# Main_Board.net
KiCad netlist of a schematic drawn in Altium Designer
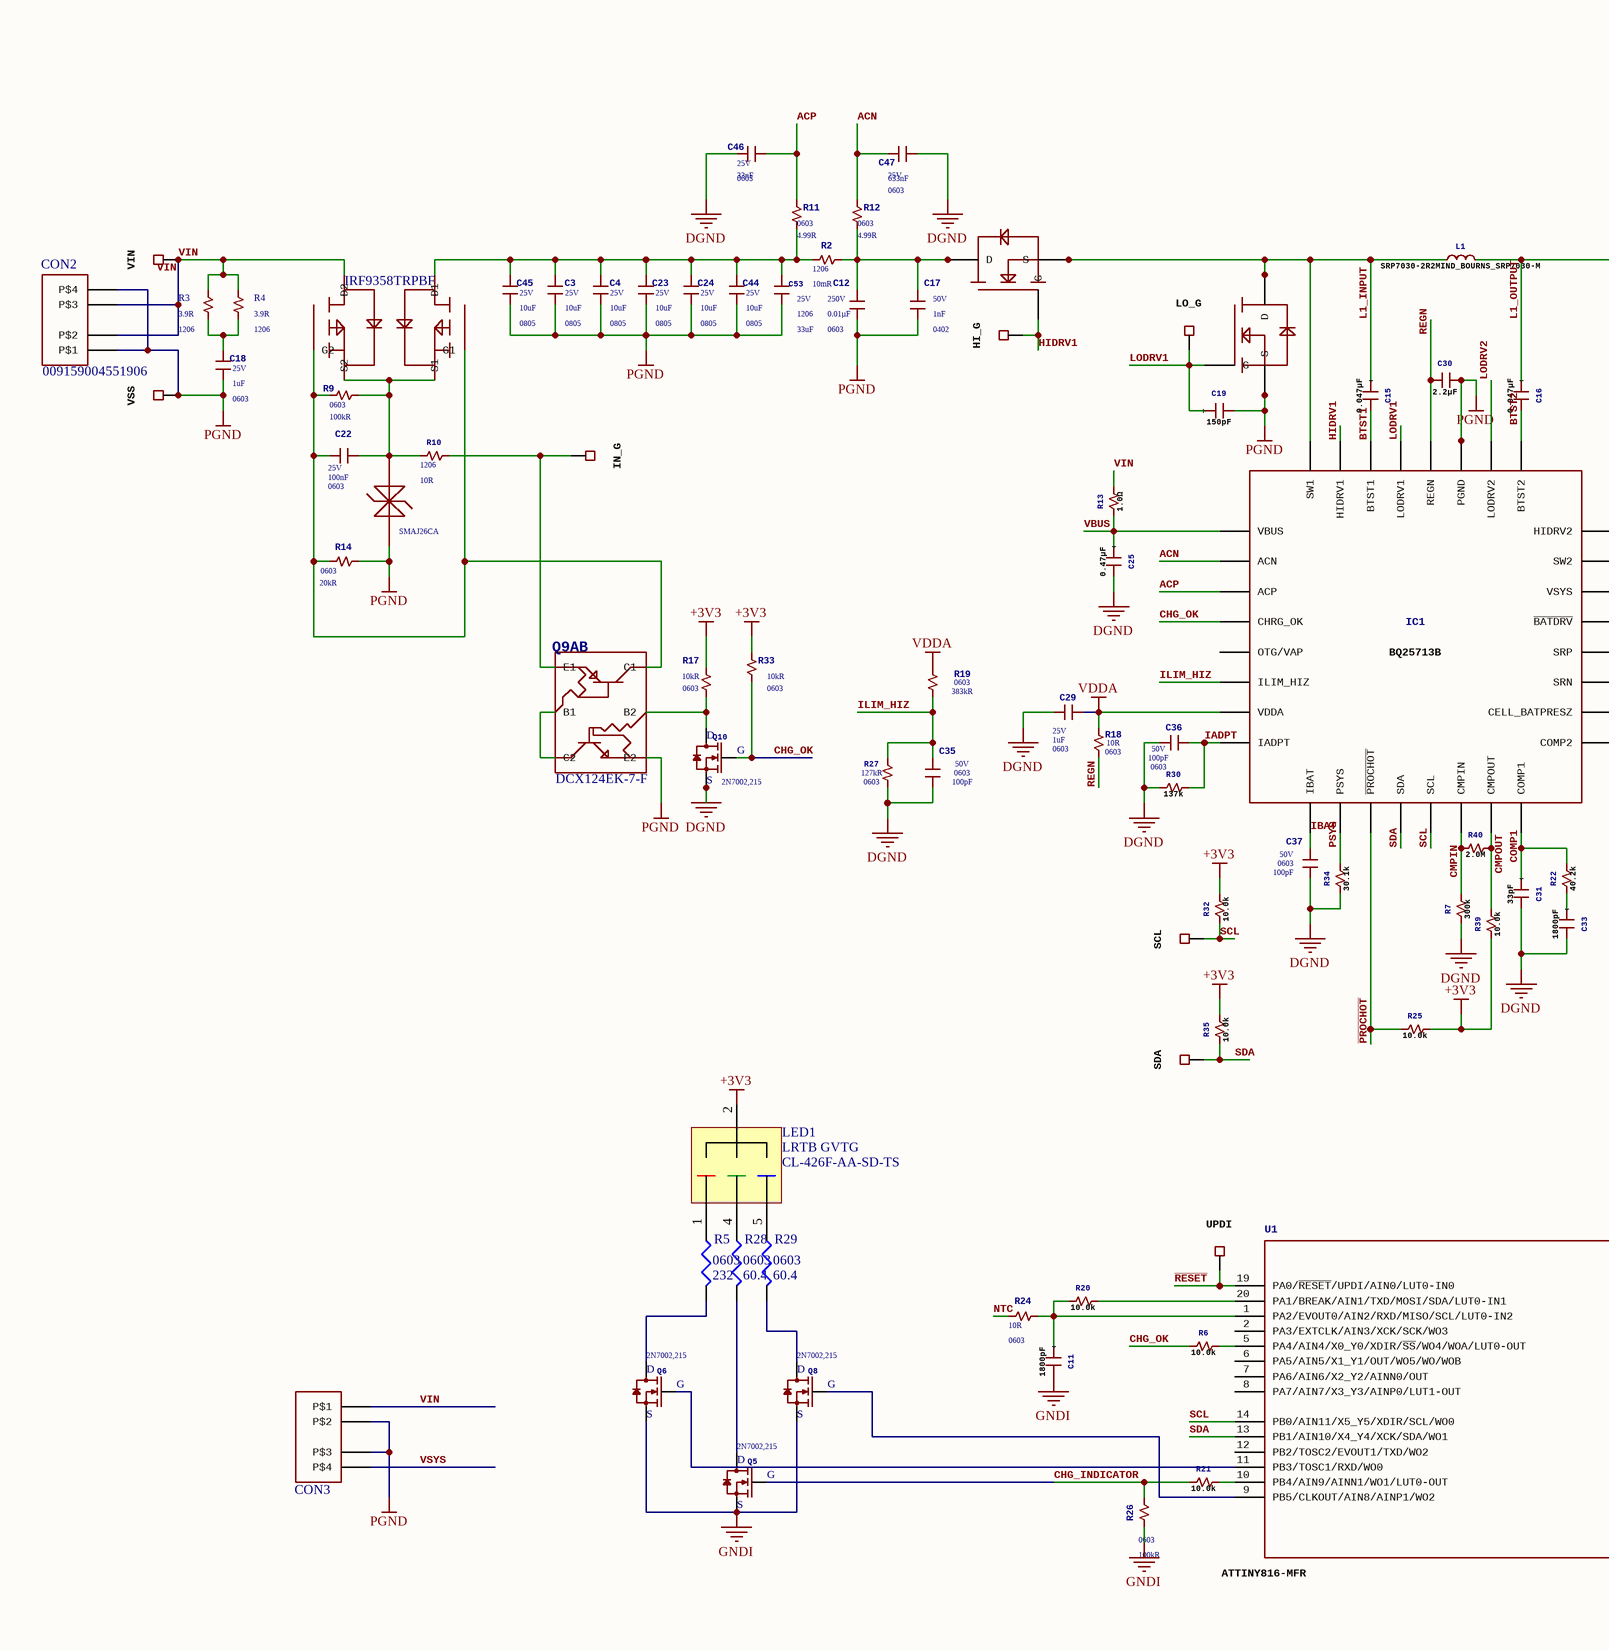
[diagram p0: Main Board.SchDoc, left]
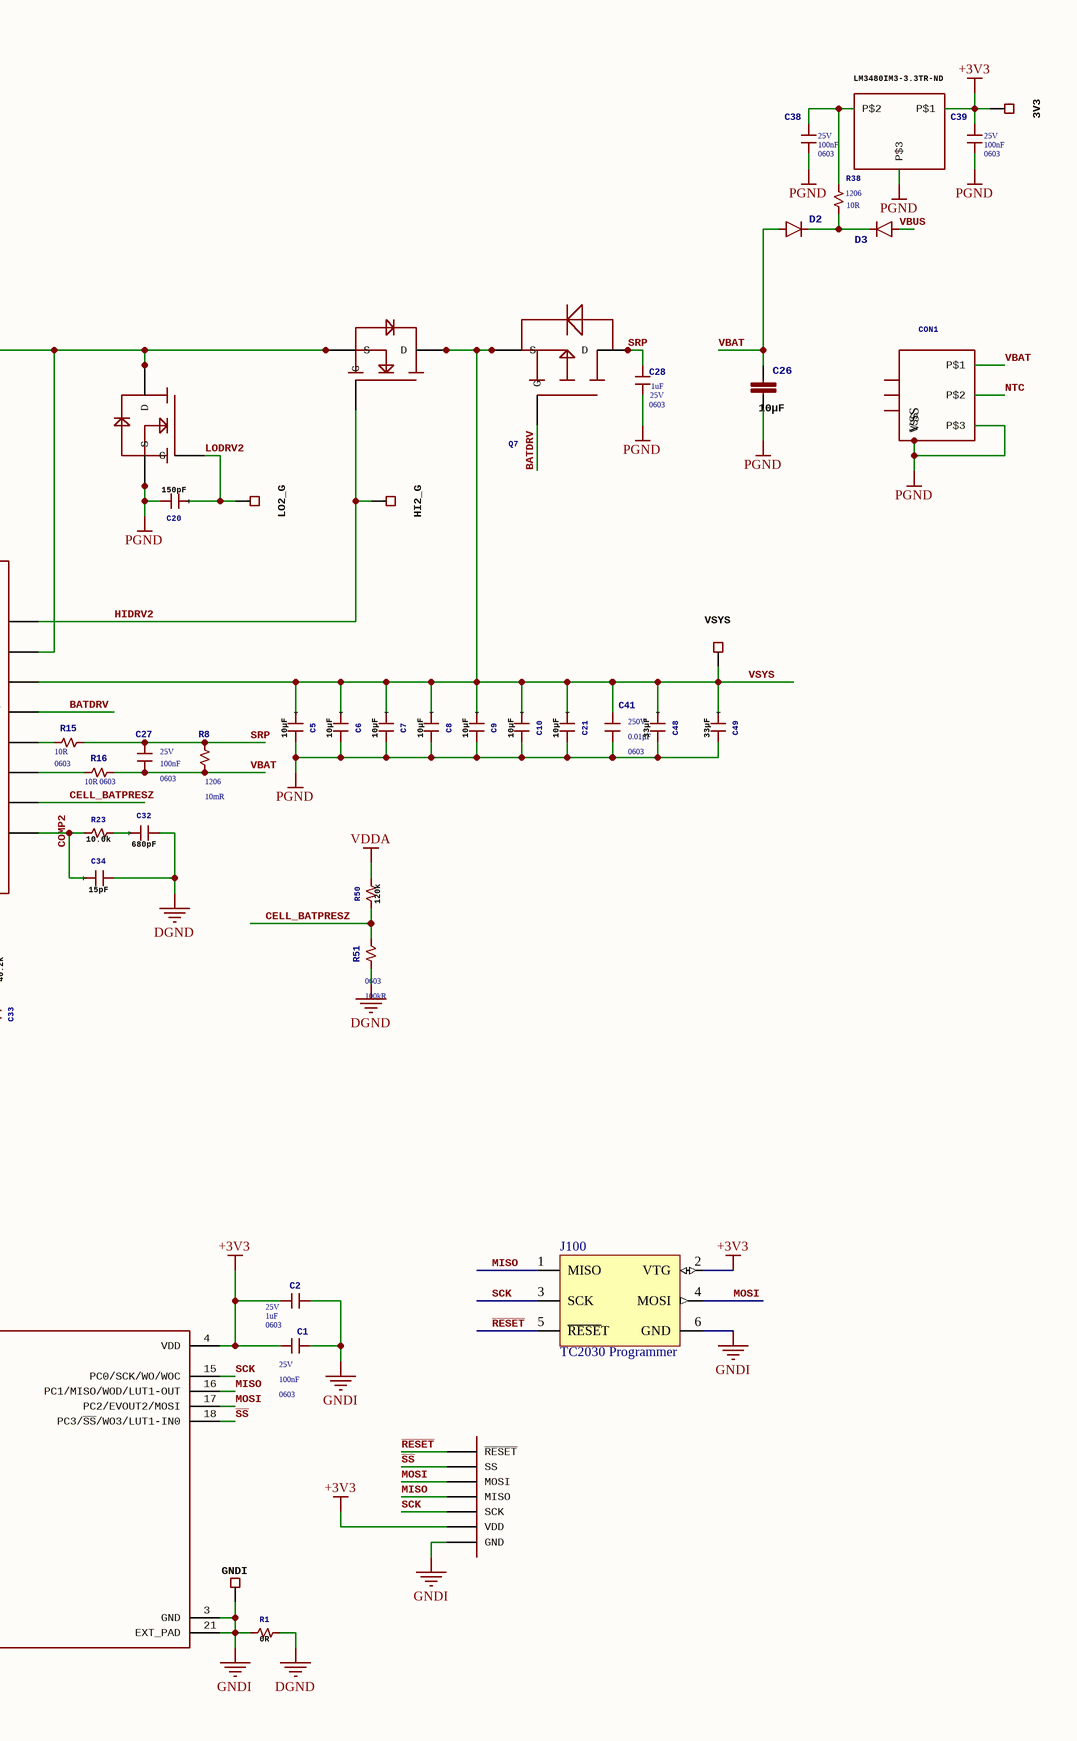
[diagram p1: Main Board.SchDoc, right]

(export (version "E")
  (design (tool "Eeschema 10.0.6"))
  (components
    (comp (ref "C1")
      (value "CAP CER 0.1UF 25V X7R 0603")
      (footprint "Main Board:0603")
      (description "0.1µF ±10% 25V Ceramic Capacitor X7R 0603 (1608 Metric)")
      (fields
        (field (name "MANUFACTURER") "TDK")
        (field (name "MANUFACTURER PART NUMBER") "CGA3E2X7R1E104K080AA")
        (field (name "VOLTAGE RATING") "25V")
        (field (name "CAPACITANCE") "100nF")
        (field (name "CASE/PACKAGE") "0603")
      )
      (libsource (lib "Main Board") (part "CGA3E2X7R1E104K080AA"))
    )
    (comp (ref "C2")
      (value "CAP CER 1UF 25V X7R 0603")
      (footprint "Main Board:0603")
      (description "1µF ±10% 25V Ceramic Capacitor X7R 0603 (1608 Metric)")
      (fields
        (field (name "MANUFACTURER") "Samsung")
        (field (name "MANUFACTURER PART NUMBER") "CL10B105KA8NNNC")
        (field (name "VOLTAGE") "25V")
        (field (name "CAPACITANCE") "1uF")
        (field (name "CASE/PACKAGE") "0603")
      )
      (libsource (lib "Main Board") (part "CL10B105KA8NNNC"))
    )
    (comp (ref "C3")
      (value "CAP CER 10UF 25V X5R 0805")
      (footprint "Main Board:0805")
      (description "10µF ±10% 25V Ceramic Capacitor X5R 0805 (2012 Metric)")
      (fields
        (field (name "MANUFACTURER") "Murata")
        (field (name "MANUFACTURER PART NUMBER") "GRM21BR61E106KA73L")
        (field (name "VOLTAGE RATING") "25V")
        (field (name "CAPACITANCE") "10uF")
        (field (name "CASE/PACKAGE") "0805")
      )
      (libsource (lib "Main Board") (part "GRM21BR61E106KA73L"))
    )
    (comp (ref "C4")
      (value "CAP CER 10UF 25V X5R 0805")
      (footprint "Main Board:0805")
      (description "10µF ±10% 25V Ceramic Capacitor X5R 0805 (2012 Metric)")
      (fields
        (field (name "MANUFACTURER") "Murata")
        (field (name "MANUFACTURER PART NUMBER") "GRM21BR61E106KA73L")
        (field (name "VOLTAGE RATING") "25V")
        (field (name "CAPACITANCE") "10uF")
        (field (name "CASE/PACKAGE") "0805")
      )
      (libsource (lib "Main Board") (part "GRM21BR61E106KA73L"))
    )
    (comp (ref "C5")
      (value "10µF")
      (footprint "0805")
      (fields (field (name "+") "+") (field (name "LIBRARYNAME") "Roambotics"))
      (libsource (lib "Roambotics") (part "SMD_CAP0805"))
    )
    (comp (ref "C6")
      (value "10µF")
      (footprint "0805")
      (fields (field (name "+") "+") (field (name "LIBRARYNAME") "Roambotics"))
      (libsource (lib "Roambotics") (part "SMD_CAP0805"))
    )
    (comp (ref "C7")
      (value "10µF")
      (footprint "0805")
      (fields (field (name "+") "+") (field (name "LIBRARYNAME") "Roambotics"))
      (libsource (lib "Roambotics") (part "SMD_CAP0805"))
    )
    (comp (ref "C8")
      (value "10µF")
      (footprint "0805")
      (fields (field (name "+") "+") (field (name "LIBRARYNAME") "Roambotics"))
      (libsource (lib "Roambotics") (part "SMD_CAP0805"))
    )
    (comp (ref "C9")
      (value "10µF")
      (footprint "0805")
      (fields (field (name "+") "+") (field (name "LIBRARYNAME") "Roambotics"))
      (libsource (lib "Roambotics") (part "SMD_CAP0805"))
    )
    (comp (ref "C10")
      (value "10µF")
      (footprint "0805")
      (fields (field (name "+") "+") (field (name "LIBRARYNAME") "Roambotics"))
      (libsource (lib "Roambotics") (part "SMD_CAP0805"))
    )
    (comp (ref "C11")
      (value "1800pF")
      (footprint "0402")
      (fields (field (name "+") "+") (field (name "LIBRARYNAME") "Roambotics"))
      (libsource (lib "Roambotics") (part "SMD_CAP0402"))
    )
    (comp (ref "C12")
      (value "CAP CER 0.01UF 250V X7R 0603")
      (footprint "Main Board:0603")
      (description "0.01µF ±10% 250V Ceramic Capacitor X7R 0603 (1608 Metric)")
      (fields
        (field (name "MANUFACTURER") "KEMET")
        (field (name "MANUFACTURER PART NUMBER") "C0603C103KARACAUTO")
        (field (name "VOLTAGE") "250V")
        (field (name "CAPACITANCE") "0.01µF")
        (field (name "PACKAGE") "0603")
      )
      (libsource (lib "Main Board") (part "C0603C103KARACAUTO"))
    )
    (comp (ref "C15")
      (value "0.047µF")
      (footprint "0603")
      (fields (field (name "+") "+") (field (name "LIBRARYNAME") "Roambotics"))
      (libsource (lib "Roambotics") (part "SMD_CAP0603"))
    )
    (comp (ref "C16")
      (value "0.047µF")
      (footprint "0603")
      (fields (field (name "+") "+") (field (name "LIBRARYNAME") "Roambotics"))
      (libsource (lib "Roambotics") (part "SMD_CAP0603"))
    )
    (comp (ref "C17")
      (value "CAP CER 1000PF 50V C0G/NP0 0402")
      (footprint "Main Board:0402")
      (description "1000pF ±5% 50V Ceramic Capacitor C0G, NP0 0402 (1005 Metric)")
      (fields
        (field (name "MANUFACTURER") "Murata")
        (field (name "MANUFACTURER PART NUMBER") "GRM1555C1H102JA01D")
        (field (name "VOLTAGE RATING") "50V")
        (field (name "CAPACITANCE") "1nF")
        (field (name "CASE/PACKAGE") "0402")
      )
      (libsource (lib "Main Board") (part "GRM1555C1H102JA01D"))
    )
    (comp (ref "C18")
      (value "CAP CER 1UF 25V X7R 0603")
      (footprint "Main Board:0603")
      (description "1µF ±10% 25V Ceramic Capacitor X7R 0603 (1608 Metric)")
      (fields
        (field (name "MANUFACTURER") "Samsung")
        (field (name "MANUFACTURER PART NUMBER") "CL10B105KA8NNNC")
        (field (name "VOLTAGE") "25V")
        (field (name "CAPACITANCE") "1uF")
        (field (name "CASE/PACKAGE") "0603")
      )
      (libsource (lib "Main Board") (part "CL10B105KA8NNNC"))
    )
    (comp (ref "C19")
      (value "150pF")
      (footprint "0603")
      (fields (field (name "+") "+") (field (name "LIBRARYNAME") "Roambotics"))
      (libsource (lib "Roambotics") (part "SMD_CAP0603"))
    )
    (comp (ref "C20")
      (value "150pF")
      (footprint "0603")
      (fields (field (name "+") "+") (field (name "LIBRARYNAME") "Roambotics"))
      (libsource (lib "Roambotics") (part "SMD_CAP0603"))
    )
    (comp (ref "C21")
      (value "10µF")
      (footprint "0805")
      (fields (field (name "+") "+") (field (name "LIBRARYNAME") "Roambotics"))
      (libsource (lib "Roambotics") (part "SMD_CAP0805"))
    )
    (comp (ref "C22")
      (value "CAP CER 0.1UF 25V X7R 0603")
      (footprint "Main Board:0603")
      (description "0.1µF ±10% 25V Ceramic Capacitor X7R 0603 (1608 Metric)")
      (fields
        (field (name "MANUFACTURER") "TDK")
        (field (name "MANUFACTURER PART NUMBER") "CGA3E2X7R1E104K080AA")
        (field (name "VOLTAGE RATING") "25V")
        (field (name "CAPACITANCE") "100nF")
        (field (name "CASE/PACKAGE") "0603")
      )
      (libsource (lib "Main Board") (part "CGA3E2X7R1E104K080AA"))
    )
    (comp (ref "C23")
      (value "CAP CER 10UF 25V X5R 0805")
      (footprint "Main Board:0805")
      (description "10µF ±10% 25V Ceramic Capacitor X5R 0805 (2012 Metric)")
      (fields
        (field (name "MANUFACTURER") "Murata")
        (field (name "MANUFACTURER PART NUMBER") "GRM21BR61E106KA73L")
        (field (name "VOLTAGE RATING") "25V")
        (field (name "CAPACITANCE") "10uF")
        (field (name "CASE/PACKAGE") "0805")
      )
      (libsource (lib "Main Board") (part "GRM21BR61E106KA73L"))
    )
    (comp (ref "C24")
      (value "CAP CER 10UF 25V X5R 0805")
      (footprint "Main Board:0805")
      (description "10µF ±10% 25V Ceramic Capacitor X5R 0805 (2012 Metric)")
      (fields
        (field (name "MANUFACTURER") "Murata")
        (field (name "MANUFACTURER PART NUMBER") "GRM21BR61E106KA73L")
        (field (name "VOLTAGE RATING") "25V")
        (field (name "CAPACITANCE") "10uF")
        (field (name "CASE/PACKAGE") "0805")
      )
      (libsource (lib "Main Board") (part "GRM21BR61E106KA73L"))
    )
    (comp (ref "C25")
      (value "0.47µF")
      (footprint "0805")
      (fields (field (name "+") "+") (field (name "LIBRARYNAME") "Roambotics"))
      (libsource (lib "Roambotics") (part "SMD_CAP0805"))
    )
    (comp (ref "C26")
      (value "10µF")
      (footprint "C1206")
      (description "CAPACITOR, European symbol")
      (libsource (lib "rcl") (part "C-EUC1206"))
    )
    (comp (ref "C27")
      (value "CAP CER 0.1UF 25V X7R 0603")
      (footprint "Main Board:0603")
      (description "0.1µF ±10% 25V Ceramic Capacitor X7R 0603 (1608 Metric)")
      (fields
        (field (name "MANUFACTURER") "TDK")
        (field (name "MANUFACTURER PART NUMBER") "CGA3E2X7R1E104K080AA")
        (field (name "VOLTAGE RATING") "25V")
        (field (name "CAPACITANCE") "100nF")
        (field (name "CASE/PACKAGE") "0603")
      )
      (libsource (lib "Main Board") (part "CGA3E2X7R1E104K080AA"))
    )
    (comp (ref "C28")
      (value "CAP CER 1UF 25V X7R 0603")
      (footprint "Main Board:0603")
      (description "1µF ±10% 25V Ceramic Capacitor X7R 0603 (1608 Metric)")
      (fields
        (field (name "MANUFACTURER") "Samsung")
        (field (name "MANUFACTURER PART NUMBER") "CL10B105KA8NNNC")
        (field (name "VOLTAGE") "25V")
        (field (name "CAPACITANCE") "1uF")
        (field (name "CASE/PACKAGE") "0603")
      )
      (libsource (lib "Main Board") (part "CL10B105KA8NNNC"))
    )
    (comp (ref "C29")
      (value "CAP CER 1UF 25V X7R 0603")
      (footprint "Main Board:0603")
      (description "1µF ±10% 25V Ceramic Capacitor X7R 0603 (1608 Metric)")
      (fields
        (field (name "MANUFACTURER") "Samsung")
        (field (name "MANUFACTURER PART NUMBER") "CL10B105KA8NNNC")
        (field (name "VOLTAGE") "25V")
        (field (name "CAPACITANCE") "1uF")
        (field (name "CASE/PACKAGE") "0603")
      )
      (libsource (lib "Main Board") (part "CL10B105KA8NNNC"))
    )
    (comp (ref "C30")
      (value "2.2µF")
      (footprint "0603")
      (fields (field (name "+") "+") (field (name "LIBRARYNAME") "Roambotics"))
      (libsource (lib "Roambotics") (part "SMD_CAP0603"))
    )
    (comp (ref "C31")
      (value "33pF")
      (footprint "0402")
      (fields (field (name "+") "+") (field (name "LIBRARYNAME") "Roambotics"))
      (libsource (lib "Roambotics") (part "SMD_CAP0402"))
    )
    (comp (ref "C32")
      (value "680pF")
      (footprint "0402")
      (fields (field (name "+") "+") (field (name "LIBRARYNAME") "Roambotics"))
      (libsource (lib "Roambotics") (part "SMD_CAP0402"))
    )
    (comp (ref "C33")
      (value "1800pF")
      (footprint "0402")
      (fields (field (name "+") "+") (field (name "LIBRARYNAME") "Roambotics"))
      (libsource (lib "Roambotics") (part "SMD_CAP0402"))
    )
    (comp (ref "C34")
      (value "15pF")
      (footprint "0402")
      (fields (field (name "+") "+") (field (name "LIBRARYNAME") "Roambotics"))
      (libsource (lib "Roambotics") (part "SMD_CAP0402"))
    )
    (comp (ref "C35")
      (value "CAP CER 100PF 50V C0G/NP0 0603")
      (footprint "Main Board:0603")
      (description "100pF ±5% 50V Ceramic Capacitor C0G, NP0 0603 (1608 Metric)")
      (fields
        (field (name "MANUFACTURER") "KEMET")
        (field (name "MANUFACTURER PART NUMBER") "C0603C101J5GACTU")
        (field (name "VOLTAGE") "50V")
        (field (name "CASE/PACKAGE") "0603")
        (field (name "CAPACITANCE") "100pF")
      )
      (libsource (lib "Main Board") (part "C0603C101J5GACTU"))
    )
    (comp (ref "C36")
      (value "CAP CER 100PF 50V C0G/NP0 0603")
      (footprint "Main Board:0603")
      (description "100pF ±5% 50V Ceramic Capacitor C0G, NP0 0603 (1608 Metric)")
      (fields
        (field (name "MANUFACTURER") "KEMET")
        (field (name "MANUFACTURER PART NUMBER") "C0603C101J5GACTU")
        (field (name "VOLTAGE") "50V")
        (field (name "CASE/PACKAGE") "0603")
        (field (name "CAPACITANCE") "100pF")
      )
      (libsource (lib "Main Board") (part "C0603C101J5GACTU"))
    )
    (comp (ref "C37")
      (value "CAP CER 100PF 50V C0G/NP0 0603")
      (footprint "Main Board:0603")
      (description "100pF ±5% 50V Ceramic Capacitor C0G, NP0 0603 (1608 Metric)")
      (fields
        (field (name "MANUFACTURER") "KEMET")
        (field (name "MANUFACTURER PART NUMBER") "C0603C101J5GACTU")
        (field (name "VOLTAGE") "50V")
        (field (name "CASE/PACKAGE") "0603")
        (field (name "CAPACITANCE") "100pF")
      )
      (libsource (lib "Main Board") (part "C0603C101J5GACTU"))
    )
    (comp (ref "C38")
      (value "CAP CER 0.1UF 25V X7R 0603")
      (footprint "Main Board:0603")
      (description "0.1µF ±10% 25V Ceramic Capacitor X7R 0603 (1608 Metric)")
      (fields
        (field (name "MANUFACTURER") "TDK")
        (field (name "MANUFACTURER PART NUMBER") "CGA3E2X7R1E104K080AA")
        (field (name "VOLTAGE RATING") "25V")
        (field (name "CAPACITANCE") "100nF")
        (field (name "CASE/PACKAGE") "0603")
      )
      (libsource (lib "Main Board") (part "CGA3E2X7R1E104K080AA"))
    )
    (comp (ref "C39")
      (value "CAP CER 0.1UF 25V X7R 0603")
      (footprint "Main Board:0603")
      (description "0.1µF ±10% 25V Ceramic Capacitor X7R 0603 (1608 Metric)")
      (fields
        (field (name "MANUFACTURER") "TDK")
        (field (name "MANUFACTURER PART NUMBER") "CGA3E2X7R1E104K080AA")
        (field (name "VOLTAGE RATING") "25V")
        (field (name "CAPACITANCE") "100nF")
        (field (name "CASE/PACKAGE") "0603")
      )
      (libsource (lib "Main Board") (part "CGA3E2X7R1E104K080AA"))
    )
    (comp (ref "C41")
      (value "CAP CER 0.01UF 250V X7R 0603")
      (footprint "Main Board:0603")
      (description "0.01µF ±10% 250V Ceramic Capacitor X7R 0603 (1608 Metric)")
      (fields
        (field (name "MANUFACTURER") "KEMET")
        (field (name "MANUFACTURER PART NUMBER") "C0603C103KARACAUTO")
        (field (name "VOLTAGE") "250V")
        (field (name "CAPACITANCE") "0.01µF")
        (field (name "PACKAGE") "0603")
      )
      (libsource (lib "Main Board") (part "C0603C103KARACAUTO"))
    )
    (comp (ref "C44")
      (value "CAP CER 10UF 25V X5R 0805")
      (footprint "Main Board:0805")
      (description "10µF ±10% 25V Ceramic Capacitor X5R 0805 (2012 Metric)")
      (fields
        (field (name "MANUFACTURER") "Murata")
        (field (name "MANUFACTURER PART NUMBER") "GRM21BR61E106KA73L")
        (field (name "VOLTAGE RATING") "25V")
        (field (name "CAPACITANCE") "10uF")
        (field (name "CASE/PACKAGE") "0805")
      )
      (libsource (lib "Main Board") (part "GRM21BR61E106KA73L"))
    )
    (comp (ref "C45")
      (value "CAP CER 10UF 25V X5R 0805")
      (footprint "Main Board:0805")
      (description "10µF ±10% 25V Ceramic Capacitor X5R 0805 (2012 Metric)")
      (fields
        (field (name "MANUFACTURER") "Murata")
        (field (name "MANUFACTURER PART NUMBER") "GRM21BR61E106KA73L")
        (field (name "VOLTAGE RATING") "25V")
        (field (name "CAPACITANCE") "10uF")
        (field (name "CASE/PACKAGE") "0805")
      )
      (libsource (lib "Main Board") (part "GRM21BR61E106KA73L"))
    )
    (comp (ref "C46")
      (value "CAP CER 0.033UF 25V X7R 0603")
      (footprint "Main Board:0603")
      (description "0.033µF ±10% 25V Ceramic Capacitor X7R 0603 (1608 Metric)")
      (fields
        (field (name "MANUFACTURER") "Samsung")
        (field (name "MANUFACTURER PART NUMBER") "CL10B333KA8NNNC")
        (field (name "VOLTAGE RATING") "25V")
        (field (name "CAPACITANCE") "33nF")
        (field (name "CASE/PACKAGE") "0603")
      )
      (libsource (lib "Main Board") (part "CL10B333KA8NNNC"))
    )
    (comp (ref "C47")
      (value "CAP CER 0.033UF 25V X7R 0603")
      (footprint "Main Board:0603")
      (description "0.033µF ±10% 25V Ceramic Capacitor X7R 0603 (1608 Metric)")
      (fields
        (field (name "MANUFACTURER") "Samsung")
        (field (name "MANUFACTURER PART NUMBER") "CL10B333KA8NNNC")
        (field (name "VOLTAGE RATING") "25V")
        (field (name "CAPACITANCE") "633nF")
        (field (name "CASE/PACKAGE") "0603")
      )
      (libsource (lib "Main Board") (part "CL10B333KA8NNNC"))
    )
    (comp (ref "C48")
      (value "33µF")
      (footprint "1206")
      (fields (field (name "+") "+") (field (name "LIBRARYNAME") "Roambotics"))
      (libsource (lib "Roambotics") (part "SMD_CAP1206"))
    )
    (comp (ref "C49")
      (value "33µF")
      (footprint "1206")
      (fields (field (name "+") "+") (field (name "LIBRARYNAME") "Roambotics"))
      (libsource (lib "Roambotics") (part "SMD_CAP1206"))
    )
    (comp (ref "C53")
      (value "CAP CER 33UF 25V X5R 1206")
      (footprint "Main Board:1206")
      (description "33µF ±20% 25V Ceramic Capacitor X5R 1206 (3216 Metric)")
      (fields
        (field (name "MANUFACTURER") "TDK")
        (field (name "MANUFACTURER PART NUMBER") "C3216X5R1E336M160AC")
        (field (name "VOLTAGE RATING") "25V")
        (field (name "CASE/PACKAGE") "1206")
        (field (name "CAPACITANCE") "33uF")
      )
      (libsource (lib "Main Board") (part "C3216X5R1E336M160AC"))
    )
    (comp (ref "CON1")
      (value "BM03B-ADHKS-GAN-ETB")
      (footprint "BM03B-ADHKS-GAN-ETB")
      (fields (field (name "LIBRARYNAME") "Roambotics"))
      (libsource (lib "Roambotics") (part "BM03B-ADHKS-GAN-ETB"))
    )
    (comp (ref "CON2")
      (value "009159004551906")
      (footprint "AVX-9159-4-PIN-EDGE")
      (description "SSL Connector 4 Position Receptacle Board to Board - Card Edge 0.079\" (2.00mm) Solder")
      (fields
        (field (name "MANUFACTURER") "Kyocera AVX")
        (field (name "MANUFACTURER PART NUMBER") "009159004551906")
      )
      (libsource (lib "Main Board") (part "CONN SSL RCPT 4POS 2MM SOLDER"))
    )
    (comp (ref "CON3")
      (value "AVX-9159-4-PIN-CARD-EDGE")
      (footprint "AVX-9159-4-PIN-EDGE")
      (fields (field (name "LIBRARYNAME") "Roambotics"))
      (libsource (lib "Roambotics") (part "AVX-9159-4-PIN-CARD-EDGE"))
    )
    (comp (ref "D1")
      (value "TVS DIODE 26V 42.1V DO214AC")
      (footprint "Main Board:DO-214AC")
      (description "42.1V Clamp 9.5A Ipp Tvs Diode Surface Mount DO-214AC (SMA)")
      (fields (field (name "MANUFACTURER") "Littelfuse") (field (name "MANUFACTURER PART NUMBER") "SMAJ26CA"))
      (libsource (lib "Main Board") (part "SMAJ26CA"))
    )
    (comp (ref "D2")
      (value "DIODE-SOD323-R")
      (footprint "SOD323-R")
      (description "DIODE")
      (libsource (lib "diode") (part "DIODE-SOD323-R"))
    )
    (comp (ref "D3")
      (value "DIODE-SOD323-R")
      (footprint "SOD323-R")
      (description "DIODE")
      (libsource (lib "diode") (part "DIODE-SOD323-R"))
    )
    (comp (ref "IC1")
      (value "BQ25713B")
      (footprint "S-PWQFN-N32")
      (fields (field (name "LIBRARYNAME") "Roambotics"))
      (libsource (lib "Roambotics") (part "BQ25713B"))
    )
    (comp (ref "J100")
      (value "TC2030 Programmer")
      (footprint "TC2030")
      (fields
        (field (name "MANUFACTURER PART NUMBER") "TC2030 6-pin programmer")
        (field (name "MANUFACTURER") "Tag-Connect")
      )
      (libsource (lib "Main Board") (part "TC2030 Programmer"))
    )
    (comp (ref "L1")
      (value "SRP7030-2R2MIND_BOURNS_SRP7030-M")
      (footprint "IND_BOURNS_SRP7030-M")
      (fields
        (field (name "MANUFACTURER_PART_NUMBER") "SRP70302R2M")
        (field (name "LIBRARYNAME") "Roambotics")
      )
      (libsource (lib "Roambotics") (part "SRP7030-2R2MIND_BOURNS_SRP7030-M"))
    )
    (comp (ref "LED1")
      (value "LRTB GVTG")
      (footprint "CL-426F-AA-SD-TS")
      (description "TRICOLOR SIDE FIRING 2.8 X 0.85")
      (fields
        (field (name "MANUFACTURER") "Citizen")
        (field (name "MANUFACTURER PART NUMBER") "CL-426F-AA-SD-TS")
      )
      (libsource (lib "Main Board") (part "CL-426F-AA-SD-TS"))
    )
    (comp (ref "PAD1")
      (value "3V3")
      (footprint "PAD")
      (fields (field (name "LIBRARYNAME") "Roambotics"))
      (libsource (lib "Roambotics") (part "1X1_PAD"))
    )
    (comp (ref "PAD2")
      (value "VIN")
      (footprint "PAD")
      (fields (field (name "LIBRARYNAME") "Roambotics"))
      (libsource (lib "Roambotics") (part "1X1_PAD"))
    )
    (comp (ref "PAD3")
      (value "VSS")
      (footprint "PAD")
      (fields (field (name "LIBRARYNAME") "Roambotics"))
      (libsource (lib "Roambotics") (part "1X1_PAD"))
    )
    (comp (ref "PAD4")
      (value "UPDI")
      (footprint "PAD")
      (fields (field (name "LIBRARYNAME") "Roambotics"))
      (libsource (lib "Roambotics") (part "1X1_PAD"))
    )
    (comp (ref "PAD5")
      (value "SCL")
      (footprint "PAD")
      (fields (field (name "LIBRARYNAME") "Roambotics"))
      (libsource (lib "Roambotics") (part "1X1_PAD"))
    )
    (comp (ref "PAD6")
      (value "SDA")
      (footprint "PAD")
      (fields (field (name "LIBRARYNAME") "Roambotics"))
      (libsource (lib "Roambotics") (part "1X1_PAD"))
    )
    (comp (ref "PAD7")
      (value "VSYS")
      (footprint "PAD")
      (fields (field (name "LIBRARYNAME") "Roambotics"))
      (libsource (lib "Roambotics") (part "1X1_PAD"))
    )
    (comp (ref "PAD10")
      (value "GNDI")
      (footprint "PAD")
      (fields (field (name "LIBRARYNAME") "Roambotics"))
      (libsource (lib "Roambotics") (part "1X1_PAD"))
    )
    (comp (ref "PAD11")
      (value "LO2_G")
      (footprint "PAD")
      (fields (field (name "LIBRARYNAME") "Roambotics"))
      (libsource (lib "Roambotics") (part "1X1_PAD"))
    )
    (comp (ref "PAD12")
      (value "IN_G")
      (footprint "PAD")
      (fields (field (name "LIBRARYNAME") "Roambotics"))
      (libsource (lib "Roambotics") (part "1X1_PAD"))
    )
    (comp (ref "PAD13")
      (value "HI_G")
      (footprint "PAD")
      (fields (field (name "LIBRARYNAME") "Roambotics"))
      (libsource (lib "Roambotics") (part "1X1_PAD"))
    )
    (comp (ref "PAD14")
      (value "LO_G")
      (footprint "PAD")
      (fields (field (name "LIBRARYNAME") "Roambotics"))
      (libsource (lib "Roambotics") (part "1X1_PAD"))
    )
    (comp (ref "PAD15")
      (value "HI2_G")
      (footprint "PAD")
      (fields (field (name "LIBRARYNAME") "Roambotics"))
      (libsource (lib "Roambotics") (part "1X1_PAD"))
    )
    (comp (ref "Q1")
      (value "CSD17551Q3A")
      (footprint "TI-Q3A")
      (fields (field (name "LIBRARYNAME") "Roambotics"))
      (libsource (lib "Main Board_1") (part "CSD17551Q3A"))
    )
    (comp (ref "Q2")
      (value "CSD17551Q3A")
      (footprint "TI-Q3A")
      (fields (field (name "LIBRARYNAME") "Roambotics"))
      (libsource (lib "Main Board_1") (part "CSD17551Q3A"))
    )
    (comp (ref "Q3")
      (value "CSD17551Q3A")
      (footprint "TI-Q3A")
      (fields (field (name "LIBRARYNAME") "Roambotics"))
      (libsource (lib "Main Board_1") (part "CSD17551Q3A"))
    )
    (comp (ref "Q4")
      (value "CSD17551Q3A")
      (footprint "TI-Q3A")
      (fields (field (name "LIBRARYNAME") "Roambotics"))
      (libsource (lib "Main Board_1") (part "CSD17551Q3A"))
    )
    (comp (ref "Q5")
      (value "2N7002,215")
      (footprint "Main Board:SOT-23")
      (description "N-Channel 60V 300mA (Ta) 830mW (Ta) Surface Mount TO-236AB")
      (fields
        (field (name "MANUFACTURER") "NXP Semiconductors")
        (field (name "VOLTAGE") "60V")
        (field (name "MANUFACTURER PART NUMBER") "2N7002,215")
      )
      (libsource (lib "Main Board") (part "MOSFET N-CH 60V 300MA SOT-23"))
    )
    (comp (ref "Q5-6")
      (value "MOSFET 2P-CH 30V 9.2A 8SOIC")
      (footprint "Main Board:INFENION_SO8")
      (description "Mosfet Array 2 P-Channel (Dual) 30V 9.2A 2W Surface Mount 8-SO")
      (fields
        (field (name "MANUFACTURER") "International Rectifier")
        (field (name "MANUFACTURER PART NUMBER") "IRF9358TRPBF")
      )
      (libsource (lib "Main Board") (part "IRF9358TRPBF"))
    )
    (comp (ref "Q6")
      (value "2N7002,215")
      (footprint "Main Board:SOT-23")
      (description "N-Channel 60V 300mA (Ta) 830mW (Ta) Surface Mount TO-236AB")
      (fields
        (field (name "MANUFACTURER") "NXP Semiconductors")
        (field (name "VOLTAGE") "60V")
        (field (name "MANUFACTURER PART NUMBER") "2N7002,215")
      )
      (libsource (lib "Main Board") (part "MOSFET N-CH 60V 300MA SOT-23"))
    )
    (comp (ref "Q7")
      (value "CSD25402Q3A")
      (footprint "TI-Q3A")
      (fields (field (name "LIBRARYNAME") "Roambotics"))
      (libsource (lib "Main Board_1") (part "CSD25402Q3A"))
    )
    (comp (ref "Q8")
      (value "2N7002,215")
      (footprint "Main Board:SOT-23")
      (description "N-Channel 60V 300mA (Ta) 830mW (Ta) Surface Mount TO-236AB")
      (fields
        (field (name "MANUFACTURER") "NXP Semiconductors")
        (field (name "VOLTAGE") "60V")
        (field (name "MANUFACTURER PART NUMBER") "2N7002,215")
      )
      (libsource (lib "Main Board") (part "MOSFET N-CH 60V 300MA SOT-23"))
    )
    (comp (ref "Q9AB")
      (value "DCX124EK-7-F")
      (footprint "Main Board:SC-74R")
      (description "TRANS NPN/PNP PREBIAS 0.3W SC74R")
      (fields (field (name "MANUFACTURER") "Diodes") (field (name "MANUFACTURER PART NUMBER") "DCX124EK-7-F"))
      (libsource (lib "Main Board") (part "DCX124EK-7-F"))
    )
    (comp (ref "Q10")
      (value "2N7002,215")
      (footprint "Main Board:SOT-23")
      (description "N-Channel 60V 300mA (Ta) 830mW (Ta) Surface Mount TO-236AB")
      (fields
        (field (name "MANUFACTURER") "NXP Semiconductors")
        (field (name "VOLTAGE") "60V")
        (field (name "MANUFACTURER PART NUMBER") "2N7002,215")
      )
      (libsource (lib "Main Board") (part "MOSFET N-CH 60V 300MA SOT-23"))
    )
    (comp (ref "R1")
      (value "0R")
      (footprint "0402")
      (fields (field (name "LIBRARYNAME") "Roambotics"))
      (libsource (lib "Roambotics") (part "SMD_RES0402"))
    )
    (comp (ref "R2")
      (value "RES 0.01 OHM 1% 1W 1206")
      (footprint "Main Board:1206")
      (fields
        (field (name "MANUFACTURER") "Vishay Dale")
        (field (name "MANUFACTURER PART NUMBER") "WSLP1206R0100FEA")
        (field (name "TOLERANCE") "1%")
        (field (name "CASE/PACKAGE") "1206")
        (field (name "RESISTANCE") "10mR")
      )
      (libsource (lib "Main Board") (part "WSLP1206R0100FEA"))
    )
    (comp (ref "R3")
      (value "RES 3.9 OHM 5% 1/4W 1206")
      (footprint "1206")
      (description "3.9 Ohms ±5% 0.25W, 1/4W Chip Resistor 1206 (3216 Metric) Automotive AEC-Q200 Thick Film")
      (fields
        (field (name "MANUFACTURER") "Stackpole Electronics")
        (field (name "MANUFACTURER PART NUMBER") "RMCF1206JT3R90")
        (field (name "CASE/PACKAGE") "1206")
        (field (name "RESISTANCE") "3.9R")
      )
      (libsource (lib "Main Board") (part "RMCF1206JT3R90"))
    )
    (comp (ref "R4")
      (value "RES 3.9 OHM 5% 1/4W 1206")
      (footprint "1206")
      (description "3.9 Ohms ±5% 0.25W, 1/4W Chip Resistor 1206 (3216 Metric) Automotive AEC-Q200 Thick Film")
      (fields
        (field (name "MANUFACTURER") "Stackpole Electronics")
        (field (name "MANUFACTURER PART NUMBER") "RMCF1206JT3R90")
        (field (name "CASE/PACKAGE") "1206")
        (field (name "RESISTANCE") "3.9R")
      )
      (libsource (lib "Main Board") (part "RMCF1206JT3R90"))
    )
    (comp (ref "R5")
      (value "RC0603FR-07232RL")
      (footprint "0603")
      (description "RES SMD 232 OHM 1% 1/10W 0603")
      (fields
        (field (name "MANUFACTURER") "Yageo")
        (field (name "PACKAGE / CASE") "0603")
        (field (name "RESISTANCE (OHMS)") "232")
        (field (name "TOLERANCE") "±1%")
      )
      (libsource (lib "Main Board") (part "RC0603FR-07232RL"))
    )
    (comp (ref "R6")
      (value "10.0k")
      (footprint "0402")
      (fields (field (name "LIBRARYNAME") "Roambotics"))
      (libsource (lib "Roambotics") (part "SMD_RES0402"))
    )
    (comp (ref "R7")
      (value "300k")
      (footprint "0603")
      (fields (field (name "LIBRARYNAME") "Roambotics"))
      (libsource (lib "Roambotics") (part "SMD_RES0603"))
    )
    (comp (ref "R8")
      (value "RES 0.01 OHM 1% 1W 1206")
      (footprint "Main Board:1206")
      (fields
        (field (name "MANUFACTURER") "Vishay Dale")
        (field (name "MANUFACTURER PART NUMBER") "WSLP1206R0100FEA")
        (field (name "TOLERANCE") "1%")
        (field (name "CASE/PACKAGE") "1206")
        (field (name "RESISTANCE") "10mR")
      )
      (libsource (lib "Main Board") (part "WSLP1206R0100FEA"))
    )
    (comp (ref "R9")
      (value "RES SMD 100K OHM 1% 1/10W 0603")
      (footprint "Main Board:0603")
      (description "100 kOhms ±1% 0.1W, 1/10W Chip Resistor 0603 (1608 Metric) Moisture Resistant Thick Film")
      (fields
        (field (name "MANUFACTURER") "Yageo")
        (field (name "MANUFACTURER PART NUMBER") "RC0603FR-07100KL")
        (field (name "CASE/PACKAGE") "0603")
        (field (name "RESISTANCE") "100kR")
      )
      (libsource (lib "Main Board") (part "RC0603FR-07100KL"))
    )
    (comp (ref "R10")
      (value "RES SMD 10 OHM 1% 1/2W 1206")
      (footprint "Main Board:1206")
      (description "10 Ohms ±1% 0.5W, 1/2W Chip Resistor 1206 (3216 Metric) Current Sense Thick Film")
      (fields
        (field (name "MANUFACTURER") "Bourns")
        (field (name "MANUFACTURER PART NUMBER") "CRM1206-FX-10R0ELF")
        (field (name "CASE/PACKAGE") "1206")
        (field (name "RESISTANCE") "10R")
      )
      (libsource (lib "Main Board") (part "CRM1206-FX-10R0ELF"))
    )
    (comp (ref "R11")
      (value "RES 4.99 OHM 1% 1/10W 0603")
      (footprint "Main Board:0603")
      (description "4.99 Ohms ±1% 0.1W, 1/10W Chip Resistor 0603 (1608 Metric) Automotive AEC-Q200 Thick Film")
      (fields
        (field (name "MANUFACTURER") "Stackpole Electronics")
        (field (name "MANUFACTURER PART NUMBER") "RMCF0603FT4R99")
        (field (name "CASE/PACKAGE") "0603")
        (field (name "RESISTANCE") "4.99R")
      )
      (libsource (lib "Main Board") (part "RMCF0603FT4R99"))
    )
    (comp (ref "R12")
      (value "RES 4.99 OHM 1% 1/10W 0603")
      (footprint "Main Board:0603")
      (description "4.99 Ohms ±1% 0.1W, 1/10W Chip Resistor 0603 (1608 Metric) Automotive AEC-Q200 Thick Film")
      (fields
        (field (name "MANUFACTURER") "Stackpole Electronics")
        (field (name "MANUFACTURER PART NUMBER") "RMCF0603FT4R99")
        (field (name "CASE/PACKAGE") "0603")
        (field (name "RESISTANCE") "4.99R")
      )
      (libsource (lib "Main Board") (part "RMCF0603FT4R99"))
    )
    (comp (ref "R13")
      (value "1.0Ω")
      (footprint "0805")
      (fields (field (name "LIBRARYNAME") "Roambotics"))
      (libsource (lib "Roambotics") (part "SMD_RES0805"))
    )
    (comp (ref "R14")
      (value "RES 20K OHM 5% 1/10W 0603")
      (footprint "Main Board:0603")
      (description "20 kOhms ±5% 0.1W, 1/10W Chip Resistor 0603 (1608 Metric) Automotive AEC-Q200 Thick Film")
      (fields
        (field (name "MANUFACTURER") "Stackpole Electronics")
        (field (name "MANUFACTURER PART NUMBER") "RMCF0603JT20K0")
        (field (name "CASE/PACKAGE") "0603")
        (field (name "RESISTANCE") "20kR")
      )
      (libsource (lib "Main Board") (part "RMCF0603JT20K0"))
    )
    (comp (ref "R15")
      (value "RES SMD 10 OHM 1% 1/10W 0603")
      (footprint "Main Board:0603")
      (description "10 Ohms ±1% 0.1W, 1/10W Chip Resistor 0603 (1608 Metric)  Thick Film")
      (fields
        (field (name "MANUFACTURER") "Vishay")
        (field (name "MANUFACTURER PART NUMBER") "CRCW060310R0FKEAC")
        (field (name "RESISTANCE") "10R")
        (field (name "CASE/PACKAGE") "0603")
      )
      (libsource (lib "Main Board") (part "CRCW060310R0FKEAC"))
    )
    (comp (ref "R16")
      (value "RES SMD 10 OHM 1% 1/10W 0603")
      (footprint "Main Board:0603")
      (description "10 Ohms ±1% 0.1W, 1/10W Chip Resistor 0603 (1608 Metric)  Thick Film")
      (fields
        (field (name "MANUFACTURER") "Vishay")
        (field (name "MANUFACTURER PART NUMBER") "CRCW060310R0FKEAC")
        (field (name "RESISTANCE") "10R")
        (field (name "CASE/PACKAGE") "0603")
      )
      (libsource (lib "Main Board") (part "CRCW060310R0FKEAC"))
    )
    (comp (ref "R17")
      (value "RES SMD 10K OHM 1% 1/10W 0603")
      (footprint "Main Board:0402")
      (description "10 kOhms ±1% 0.1W, 1/10W Chip Resistor 0603 (1608 Metric) Automotive AEC-Q200 Thick Film")
      (fields
        (field (name "MANUFACTURER") "Vishay")
        (field (name "MANUFACTURER PART NUMBER") "CRCW060310K0FKEAHP")
        (field (name "RESISTANCE") "10kR")
        (field (name "CASE/PACKAGE") "0603")
      )
      (libsource (lib "Main Board") (part "CRCW060310K0FKEA"))
    )
    (comp (ref "R18")
      (value "RES SMD 10 OHM 1% 1/10W 0603")
      (footprint "Main Board:0603")
      (description "10 Ohms ±1% 0.1W, 1/10W Chip Resistor 0603 (1608 Metric)  Thick Film")
      (fields
        (field (name "MANUFACTURER") "Vishay")
        (field (name "MANUFACTURER PART NUMBER") "CRCW060310R0FKEAC")
        (field (name "RESISTANCE") "10R")
        (field (name "CASE/PACKAGE") "0603")
      )
      (libsource (lib "Main Board") (part "CRCW060310R0FKEAC"))
    )
    (comp (ref "R19")
      (value "RES SMD 383K OHM 1% 1/10W 0603")
      (footprint "Main Board:0603")
      (description "383 kOhms ±1% 0.1W, 1/10W Chip Resistor 0603 (1608 Metric) Moisture Resistant Thick Film")
      (fields
        (field (name "MANUFACTURER") "Yageo")
        (field (name "MANUFACTURER PART NUMBER") "RC0603FR-07383KL")
        (field (name "CASE/PACKAGE") "0603")
        (field (name "RESISTANCE") "383kR")
      )
      (libsource (lib "Main Board") (part "RC0603FR-07383KL"))
    )
    (comp (ref "R20")
      (value "10.0k")
      (footprint "0402")
      (fields (field (name "LIBRARYNAME") "Roambotics"))
      (libsource (lib "Roambotics") (part "SMD_RES0402"))
    )
    (comp (ref "R21")
      (value "10.0k")
      (footprint "0402")
      (fields (field (name "LIBRARYNAME") "Roambotics"))
      (libsource (lib "Roambotics") (part "SMD_RES0402"))
    )
    (comp (ref "R22")
      (value "40.2k")
      (footprint "0402")
      (fields (field (name "LIBRARYNAME") "Roambotics"))
      (libsource (lib "Roambotics") (part "SMD_RES0402"))
    )
    (comp (ref "R23")
      (value "10.0k")
      (footprint "0402")
      (fields (field (name "LIBRARYNAME") "Roambotics"))
      (libsource (lib "Roambotics") (part "SMD_RES0402"))
    )
    (comp (ref "R24")
      (value "RES SMD 10 OHM 1% 1/10W 0603")
      (footprint "Main Board:0603")
      (description "10 Ohms ±1% 0.1W, 1/10W Chip Resistor 0603 (1608 Metric)  Thick Film")
      (fields
        (field (name "MANUFACTURER") "Vishay")
        (field (name "MANUFACTURER PART NUMBER") "CRCW060310R0FKEAC")
        (field (name "RESISTANCE") "10R")
        (field (name "CASE/PACKAGE") "0603")
      )
      (libsource (lib "Main Board") (part "CRCW060310R0FKEAC"))
    )
    (comp (ref "R25")
      (value "10.0k")
      (footprint "0603")
      (fields (field (name "LIBRARYNAME") "Roambotics"))
      (libsource (lib "Roambotics") (part "SMD_RES0603"))
    )
    (comp (ref "R26")
      (value "RES SMD 100K OHM 1% 1/10W 0603")
      (footprint "Main Board:0603")
      (description "100 kOhms ±1% 0.1W, 1/10W Chip Resistor 0603 (1608 Metric) Moisture Resistant Thick Film")
      (fields
        (field (name "MANUFACTURER") "Yageo")
        (field (name "MANUFACTURER PART NUMBER") "RC0603FR-07100KL")
        (field (name "CASE/PACKAGE") "0603")
        (field (name "RESISTANCE") "100kR")
      )
      (libsource (lib "Main Board") (part "RC0603FR-07100KL"))
    )
    (comp (ref "R27")
      (value "RES SMD 127K OHM 1% 1/10W 0603")
      (footprint "Main Board:0603")
      (description "127 kOhms ±1% 0.1W, 1/10W Chip Resistor 0603 (1608 Metric) Moisture Resistant Thick Film")
      (fields
        (field (name "MANUFACTURER") "Yageo")
        (field (name "MANUFACTURER PART NUMBER") "RC0603FR-07127KL")
        (field (name "RESISTANCE") "127kR")
        (field (name "CASE/PACKAGE") "0603")
      )
      (libsource (lib "Main Board") (part "RC0603FR-07127KL"))
    )
    (comp (ref "R28")
      (value "RC0603FR-0760R4L")
      (footprint "0603")
      (description "RES SMD 60.4 OHM 1% 1/10W 0603")
      (fields
        (field (name "MANUFACTURER") "Yageo")
        (field (name "PACKAGE / CASE") "0603")
        (field (name "RESISTANCE (OHMS)") "60.4")
        (field (name "TOLERANCE") "±1%")
      )
      (libsource (lib "Main Board") (part "RC0603FR-0760R4L"))
    )
    (comp (ref "R29")
      (value "RC0603FR-0760R4L")
      (footprint "0603")
      (description "RES SMD 60.4 OHM 1% 1/10W 0603")
      (fields
        (field (name "MANUFACTURER") "Yageo")
        (field (name "PACKAGE / CASE") "0603")
        (field (name "RESISTANCE (OHMS)") "60.4")
        (field (name "TOLERANCE") "±1%")
      )
      (libsource (lib "Main Board") (part "RC0603FR-0760R4L"))
    )
    (comp (ref "R30")
      (value "137k")
      (footprint "0603")
      (fields (field (name "LIBRARYNAME") "Roambotics"))
      (libsource (lib "Roambotics") (part "SMD_RES0603"))
    )
    (comp (ref "R32")
      (value "10.0k")
      (footprint "0603")
      (fields (field (name "LIBRARYNAME") "Roambotics"))
      (libsource (lib "Roambotics") (part "SMD_RES0603"))
    )
    (comp (ref "R33")
      (value "RES SMD 10K OHM 1% 1/10W 0603")
      (footprint "Main Board:0402")
      (description "10 kOhms ±1% 0.1W, 1/10W Chip Resistor 0603 (1608 Metric) Automotive AEC-Q200 Thick Film")
      (fields
        (field (name "MANUFACTURER") "Vishay")
        (field (name "MANUFACTURER PART NUMBER") "CRCW060310K0FKEAHP")
        (field (name "RESISTANCE") "10kR")
        (field (name "CASE/PACKAGE") "0603")
      )
      (libsource (lib "Main Board") (part "CRCW060310K0FKEA"))
    )
    (comp (ref "R34")
      (value "30.1k")
      (footprint "0603")
      (fields (field (name "LIBRARYNAME") "Roambotics"))
      (libsource (lib "Roambotics") (part "SMD_RES0603"))
    )
    (comp (ref "R35")
      (value "10.0k")
      (footprint "0603")
      (fields (field (name "LIBRARYNAME") "Roambotics"))
      (libsource (lib "Roambotics") (part "SMD_RES0603"))
    )
    (comp (ref "R38")
      (value "RES SMD 10 OHM 1% 1/2W 1206")
      (footprint "Main Board:1206")
      (description "10 Ohms ±1% 0.5W, 1/2W Chip Resistor 1206 (3216 Metric) Current Sense Thick Film")
      (fields
        (field (name "MANUFACTURER") "Bourns")
        (field (name "MANUFACTURER PART NUMBER") "CRM1206-FX-10R0ELF")
        (field (name "CASE/PACKAGE") "1206")
        (field (name "RESISTANCE") "10R")
      )
      (libsource (lib "Main Board") (part "CRM1206-FX-10R0ELF"))
    )
    (comp (ref "R39")
      (value "10.0k")
      (footprint "0603")
      (fields (field (name "LIBRARYNAME") "Roambotics"))
      (libsource (lib "Roambotics") (part "SMD_RES0603"))
    )
    (comp (ref "R40")
      (value "2.0M")
      (footprint "0603")
      (fields (field (name "LIBRARYNAME") "Roambotics"))
      (libsource (lib "Roambotics") (part "SMD_RES0603"))
    )
    (comp (ref "R50")
      (value "120k")
      (footprint "0603")
      (fields (field (name "LIBRARYNAME") "Roambotics"))
      (libsource (lib "Roambotics") (part "SMD_RES0603"))
    )
    (comp (ref "R51")
      (value "RES SMD 100K OHM 1% 1/10W 0603")
      (footprint "Main Board:0603")
      (description "100 kOhms ±1% 0.1W, 1/10W Chip Resistor 0603 (1608 Metric) Moisture Resistant Thick Film")
      (fields
        (field (name "MANUFACTURER") "Yageo")
        (field (name "MANUFACTURER PART NUMBER") "RC0603FR-07100KL")
        (field (name "CASE/PACKAGE") "0603")
        (field (name "RESISTANCE") "100kR")
      )
      (libsource (lib "Main Board") (part "RC0603FR-07100KL"))
    )
    (comp (ref "U$1")
      (value "ATTINY_DEBUG")
      (footprint "ATTINY_DEBUG")
      (fields (field (name "LIBRARYNAME") "Roambotics"))
      (libsource (lib "Roambotics") (part "ATTINY_DEBUG"))
    )
    (comp (ref "U1")
      (value "ATTINY816-MFR")
      (footprint "QFN40P300X300X90-21N")
      (description "Mcu, 8bit, Pic24fj, 20mhz, Qfn-20")
      (fields (field (name "DIGI-KEY_PART_NUMBER") "ATTINY816-MFRCT-ND") (field (name "MF") "Microchip"))
      (libsource (lib "ATTINY816-MFR") (part "ATTINY816-MFR"))
    )
    (comp (ref "U2")
      (value "LM3480IM3-3.3TR-ND")
      (footprint "Main Board:SOT-23_2")
      (fields
        (field (name "LM3480IM3-3.3TR-ND") "LM3480IM3-3.3TR-ND")
        (field (name "LIBRARYNAME") "Roambotics")
      )
      (libsource (lib "Roambotics") (part "LM3480IM3-3.3TR-ND"))
    )
  )
  (nets
    (net (code "1") (name "+3V3") (class "Default")
      (node (ref "C1") (pin "P$1") (pinfunction "P$1_P$1") (pintype "passive"))
      (node (ref "C2") (pin "P$2") (pinfunction "P$2_P$2") (pintype "passive"))
      (node (ref "C39") (pin "P$2") (pinfunction "P$2_P$2") (pintype "passive"))
      (node (ref "J100") (pin "2") (pinfunction "VTG_2") (pintype "bidirectional"))
      (node (ref "LED1") (pin "2") (pintype "power_in"))
      (node (ref "PAD1") (pin "P$1") (pinfunction "P$1_P$1") (pintype "passive"))
      (node (ref "R17") (pin "P$2") (pinfunction "P$2_P$2") (pintype "passive"))
      (node (ref "R25") (pin "P$2") (pinfunction "P$2_P$2") (pintype "passive"))
      (node (ref "R32") (pin "P$2") (pinfunction "P$2_P$2") (pintype "passive"))
      (node (ref "R33") (pin "P$2") (pinfunction "P$2_P$2") (pintype "passive"))
      (node (ref "R35") (pin "P$2") (pinfunction "P$2_P$2") (pintype "passive"))
      (node (ref "R39") (pin "P$1") (pinfunction "P$1_P$1") (pintype "passive"))
      (node (ref "U$1") (pin "P$2") (pinfunction "VDD_P$2") (pintype "passive"))
      (node (ref "U1") (pin "4") (pinfunction "VDD_4") (pintype "power_in"))
      (node (ref "U2") (pin "P$1") (pinfunction "P$1_P$1") (pintype "passive"))
    )
    (net (code "2") (name "/ACN") (class "Default")
      (node (ref "C47") (pin "P$1") (pinfunction "P$1_P$1") (pintype "passive"))
      (node (ref "IC1") (pin "P$2") (pinfunction "ACN_P$2") (pintype "passive"))
      (node (ref "R12") (pin "P$2") (pinfunction "P$2_P$2") (pintype "passive"))
    )
    (net (code "3") (name "/ACP") (class "Default")
      (node (ref "C46") (pin "P$2") (pinfunction "P$2_P$2") (pintype "passive"))
      (node (ref "IC1") (pin "P$3") (pinfunction "ACP_P$3") (pintype "passive"))
      (node (ref "R11") (pin "P$2") (pinfunction "P$2_P$2") (pintype "passive"))
    )
    (net (code "4") (name "/BATDRV") (class "Default")
      (node (ref "IC1") (pin "P$21") (pinfunction "~{BATDRV}_P$21") (pintype "passive"))
      (node (ref "Q7") (pin "P$4") (pinfunction "G_P$4") (pintype "passive"))
    )
    (net (code "5") (name "/BTST1") (class "Default")
      (node (ref "C15") (pin "P$2") (pinfunction "P$2_P$2") (pintype "passive"))
      (node (ref "IC1") (pin "P$30") (pinfunction "BTST1_P$30") (pintype "passive"))
    )
    (net (code "6") (name "/BTST2") (class "Default")
      (node (ref "C16") (pin "P$2") (pinfunction "P$2_P$2") (pintype "passive"))
      (node (ref "IC1") (pin "P$25") (pinfunction "BTST2_P$25") (pintype "passive"))
    )
    (net (code "7") (name "/CELL_BATPRESZ") (class "Default")
      (node (ref "IC1") (pin "P$18") (pinfunction "CELL_BATPRESZ_P$18") (pintype "passive"))
      (node (ref "R50") (pin "P$1") (pinfunction "P$1_P$1") (pintype "passive"))
      (node (ref "R51") (pin "P$2") (pinfunction "P$2_P$2") (pintype "passive"))
    )
    (net (code "8") (name "/CHG_INDICATOR") (class "Default")
      (node (ref "Q5") (pin "1") (pinfunction "G_1") (pintype "passive"))
      (node (ref "R21") (pin "P$1") (pinfunction "P$1_P$1") (pintype "passive"))
      (node (ref "R26") (pin "P$2") (pinfunction "P$2_P$2") (pintype "passive"))
    )
    (net (code "9") (name "/CHG_OK") (class "Default")
      (node (ref "IC1") (pin "P$4") (pinfunction "CHRG_OK_P$4") (pintype "passive"))
      (node (ref "Q10") (pin "1") (pinfunction "G_1") (pintype "passive"))
      (node (ref "R33") (pin "P$1") (pinfunction "P$1_P$1") (pintype "passive"))
      (node (ref "R6") (pin "P$1") (pinfunction "P$1_P$1") (pintype "passive"))
    )
    (net (code "10") (name "/CMPIN") (class "Default")
      (node (ref "IC1") (pin "P$14") (pinfunction "CMPIN_P$14") (pintype "passive"))
      (node (ref "R40") (pin "P$1") (pinfunction "P$1_P$1") (pintype "passive"))
      (node (ref "R7") (pin "P$2") (pinfunction "P$2_P$2") (pintype "passive"))
    )
    (net (code "11") (name "/CMPOUT") (class "Default")
      (node (ref "IC1") (pin "P$15") (pinfunction "CMPOUT_P$15") (pintype "passive"))
      (node (ref "R39") (pin "P$2") (pinfunction "P$2_P$2") (pintype "passive"))
      (node (ref "R40") (pin "P$2") (pinfunction "P$2_P$2") (pintype "passive"))
    )
    (net (code "12") (name "/COMP1") (class "Default")
      (node (ref "C31") (pin "P$1") (pinfunction "P$1_P$1") (pintype "passive"))
      (node (ref "IC1") (pin "P$16") (pinfunction "COMP1_P$16") (pintype "passive"))
      (node (ref "R22") (pin "P$2") (pinfunction "P$2_P$2") (pintype "passive"))
    )
    (net (code "13") (name "/COMP2") (class "Default")
      (node (ref "C34") (pin "P$1") (pinfunction "P$1_P$1") (pintype "passive"))
      (node (ref "IC1") (pin "P$17") (pinfunction "COMP2_P$17") (pintype "passive"))
      (node (ref "R23") (pin "P$1") (pinfunction "P$1_P$1") (pintype "passive"))
    )
    (net (code "14") (name "/HIDRV1") (class "Default")
      (node (ref "IC1") (pin "P$31") (pinfunction "HIDRV1_P$31") (pintype "passive"))
      (node (ref "PAD13") (pin "P$1") (pinfunction "P$1_P$1") (pintype "passive"))
      (node (ref "Q1") (pin "P$4") (pinfunction "G_P$4") (pintype "passive"))
    )
    (net (code "15") (name "/HIDRV2") (class "Default")
      (node (ref "IC1") (pin "P$24") (pinfunction "HIDRV2_P$24") (pintype "passive"))
      (node (ref "PAD15") (pin "P$1") (pinfunction "P$1_P$1") (pintype "passive"))
      (node (ref "Q4") (pin "P$4") (pinfunction "G_P$4") (pintype "passive"))
    )
    (net (code "16") (name "/IADPT") (class "Default")
      (node (ref "C36") (pin "P$2") (pinfunction "P$2_P$2") (pintype "passive"))
      (node (ref "IC1") (pin "P$8") (pinfunction "IADPT_P$8") (pintype "passive"))
      (node (ref "R30") (pin "P$2") (pinfunction "P$2_P$2") (pintype "passive"))
    )
    (net (code "17") (name "/IBAT") (class "Default")
      (node (ref "C37") (pin "P$2") (pinfunction "P$2_P$2") (pintype "passive"))
      (node (ref "IC1") (pin "P$9") (pinfunction "IBAT_P$9") (pintype "passive"))
    )
    (net (code "18") (name "/ILIM_HIZ") (class "Default")
      (node (ref "C35") (pin "P$2") (pinfunction "P$2_P$2") (pintype "passive"))
      (node (ref "IC1") (pin "P$6") (pinfunction "ILIM_HIZ_P$6") (pintype "passive"))
      (node (ref "R19") (pin "P$1") (pinfunction "P$1_P$1") (pintype "passive"))
      (node (ref "R27") (pin "P$2") (pinfunction "P$2_P$2") (pintype "passive"))
    )
    (net (code "19") (name "/L1_INPUT") (class "Default")
      (node (ref "C15") (pin "P$1") (pinfunction "P$1_P$1") (pintype "passive"))
      (node (ref "IC1") (pin "P$32") (pinfunction "SW1_P$32") (pintype "passive"))
      (node (ref "L1") (pin "1") (pinfunction "P$1_1") (pintype "passive"))
      (node (ref "Q1") (pin "P$1") (pinfunction "S_P$1") (pintype "passive"))
      (node (ref "Q1") (pin "P$2") (pinfunction "S_P$2") (pintype "passive"))
      (node (ref "Q1") (pin "P$3") (pinfunction "S_P$3") (pintype "passive"))
      (node (ref "Q2") (pin "P$5") (pinfunction "D_P$5") (pintype "passive"))
      (node (ref "Q2") (pin "P$6") (pinfunction "D_P$6") (pintype "passive"))
      (node (ref "Q2") (pin "P$7") (pinfunction "D_P$7") (pintype "passive"))
      (node (ref "Q2") (pin "P$8") (pinfunction "D_P$8") (pintype "passive"))
      (node (ref "Q2") (pin "P$9") (pinfunction "D_P$9") (pintype "passive"))
    )
    (net (code "20") (name "/L1_OUTPUT") (class "Default")
      (node (ref "C16") (pin "P$1") (pinfunction "P$1_P$1") (pintype "passive"))
      (node (ref "IC1") (pin "P$23") (pinfunction "SW2_P$23") (pintype "passive"))
      (node (ref "L1") (pin "2") (pinfunction "P$2_2") (pintype "passive"))
      (node (ref "Q3") (pin "P$5") (pinfunction "D_P$5") (pintype "passive"))
      (node (ref "Q3") (pin "P$6") (pinfunction "D_P$6") (pintype "passive"))
      (node (ref "Q3") (pin "P$7") (pinfunction "D_P$7") (pintype "passive"))
      (node (ref "Q3") (pin "P$8") (pinfunction "D_P$8") (pintype "passive"))
      (node (ref "Q3") (pin "P$9") (pinfunction "D_P$9") (pintype "passive"))
      (node (ref "Q4") (pin "P$1") (pinfunction "S_P$1") (pintype "passive"))
      (node (ref "Q4") (pin "P$2") (pinfunction "S_P$2") (pintype "passive"))
      (node (ref "Q4") (pin "P$3") (pinfunction "S_P$3") (pintype "passive"))
    )
    (net (code "21") (name "/LODRV1") (class "Default")
      (node (ref "C19") (pin "P$1") (pinfunction "P$1_P$1") (pintype "passive"))
      (node (ref "IC1") (pin "P$29") (pinfunction "LODRV1_P$29") (pintype "passive"))
      (node (ref "PAD14") (pin "P$1") (pinfunction "P$1_P$1") (pintype "passive"))
      (node (ref "Q2") (pin "P$4") (pinfunction "G_P$4") (pintype "passive"))
    )
    (net (code "22") (name "/LODRV2") (class "Default")
      (node (ref "C20") (pin "P$1") (pinfunction "P$1_P$1") (pintype "passive"))
      (node (ref "IC1") (pin "P$26") (pinfunction "LODRV2_P$26") (pintype "passive"))
      (node (ref "PAD11") (pin "P$1") (pinfunction "P$1_P$1") (pintype "passive"))
      (node (ref "Q3") (pin "P$4") (pinfunction "G_P$4") (pintype "passive"))
    )
    (net (code "23") (name "/MISO") (class "Default")
      (node (ref "J100") (pin "1") (pinfunction "MISO_1") (pintype "power_in"))
      (node (ref "U$1") (pin "P$4") (pinfunction "MISO_P$4") (pintype "passive"))
      (node (ref "U1") (pin "16") (pinfunction "PC1/MISO/WOD/LUT1-OUT_16") (pintype "passive"))
    )
    (net (code "24") (name "/MOSI") (class "Default")
      (node (ref "J100") (pin "4") (pinfunction "MOSI_4") (pintype "output"))
      (node (ref "U$1") (pin "P$5") (pinfunction "MOSI_P$5") (pintype "passive"))
      (node (ref "U1") (pin "17") (pinfunction "PC2/EVOUT2/MOSI_17") (pintype "passive"))
    )
    (net (code "25") (name "/NTC") (class "Default")
      (node (ref "CON1") (pin "P$2") (pinfunction "P$2_P$2") (pintype "passive"))
      (node (ref "R24") (pin "P$2") (pinfunction "P$2_P$2") (pintype "passive"))
    )
    (net (code "26") (name "/PSYS") (class "Default")
      (node (ref "IC1") (pin "P$10") (pinfunction "PSYS_P$10") (pintype "passive"))
      (node (ref "R34") (pin "P$2") (pinfunction "P$2_P$2") (pintype "passive"))
    )
    (net (code "27") (name "/REGN") (class "Default")
      (node (ref "C30") (pin "P$1") (pinfunction "P$1_P$1") (pintype "passive"))
      (node (ref "IC1") (pin "P$28") (pinfunction "REGN_P$28") (pintype "passive"))
      (node (ref "R18") (pin "P$1") (pinfunction "P$1_P$1") (pintype "passive"))
    )
    (net (code "28") (name "/SCK") (class "Default")
      (node (ref "J100") (pin "3") (pinfunction "SCK_3") (pintype "passive"))
      (node (ref "U$1") (pin "P$3") (pinfunction "SCK_P$3") (pintype "passive"))
      (node (ref "U1") (pin "15") (pinfunction "PC0/SCK/WO/WOC_15") (pintype "passive"))
    )
    (net (code "29") (name "/SCL") (class "Default")
      (node (ref "IC1") (pin "P$13") (pinfunction "SCL_P$13") (pintype "passive"))
      (node (ref "PAD5") (pin "P$1") (pinfunction "P$1_P$1") (pintype "passive"))
      (node (ref "R32") (pin "P$1") (pinfunction "P$1_P$1") (pintype "passive"))
      (node (ref "U1") (pin "14") (pinfunction "PB0/AIN11/X5_Y5/XDIR/SCL/WO0_14") (pintype "passive"))
    )
    (net (code "30") (name "/SDA") (class "Default")
      (node (ref "IC1") (pin "P$12") (pinfunction "SDA_P$12") (pintype "passive"))
      (node (ref "PAD6") (pin "P$1") (pinfunction "P$1_P$1") (pintype "passive"))
      (node (ref "R35") (pin "P$1") (pinfunction "P$1_P$1") (pintype "passive"))
      (node (ref "U1") (pin "13") (pinfunction "PB1/AIN10/X4_Y4/XCK/SDA/WO1_13") (pintype "passive"))
    )
    (net (code "31") (name "/SRP") (class "Default")
      (node (ref "C27") (pin "P$2") (pinfunction "P$2_P$2") (pintype "passive"))
      (node (ref "C28") (pin "P$2") (pinfunction "P$2_P$2") (pintype "passive"))
      (node (ref "Q7") (pin "P$1") (pinfunction "D_P$1") (pintype "passive"))
      (node (ref "Q7") (pin "P$2") (pinfunction "D_P$2") (pintype "passive"))
      (node (ref "Q7") (pin "P$3") (pinfunction "D_P$3") (pintype "passive"))
      (node (ref "R15") (pin "P$2") (pinfunction "P$2_P$2") (pintype "passive"))
      (node (ref "R8") (pin "P$2") (pinfunction "P$2_P$2") (pintype "passive"))
    )
    (net (code "32") (name "/VBAT") (class "Default")
      (node (ref "C26") (pin "1") (pinfunction "1_1") (pintype "passive"))
      (node (ref "C27") (pin "P$1") (pinfunction "P$1_P$1") (pintype "passive"))
      (node (ref "CON1") (pin "P$1") (pinfunction "P$1_P$1") (pintype "passive"))
      (node (ref "D2") (pin "A") (pinfunction "A_A") (pintype "passive"))
      (node (ref "R16") (pin "P$2") (pinfunction "P$2_P$2") (pintype "passive"))
      (node (ref "R8") (pin "P$1") (pinfunction "P$1_P$1") (pintype "passive"))
    )
    (net (code "33") (name "/VBUS") (class "Default")
      (node (ref "C25") (pin "P$1") (pinfunction "P$1_P$1") (pintype "passive"))
      (node (ref "D3") (pin "A") (pinfunction "A_A") (pintype "passive"))
      (node (ref "IC1") (pin "P$1") (pinfunction "VBUS_P$1") (pintype "passive"))
      (node (ref "R13") (pin "P$1") (pinfunction "P$1_P$1") (pintype "passive"))
    )
    (net (code "34") (name "/VIN") (class "Default")
      (node (ref "CON2") (pin "P$2") (pinfunction "P$2_P$2") (pintype "passive"))
      (node (ref "CON2") (pin "P$3") (pinfunction "P$3_P$3") (pintype "passive"))
      (node (ref "CON3") (pin "P$1") (pinfunction "P$1_P$1") (pintype "passive"))
      (node (ref "PAD2") (pin "P$1") (pinfunction "P$1_P$1") (pintype "passive"))
      (node (ref "Q5-6") (pin "P$7_P$8") (pinfunction "D2_P$7_P$8") (pintype "passive"))
      (node (ref "R13") (pin "P$2") (pinfunction "P$2_P$2") (pintype "passive"))
      (node (ref "R3") (pin "P$2") (pinfunction "P$2_P$2") (pintype "passive"))
      (node (ref "R4") (pin "P$2") (pinfunction "P$2_P$2") (pintype "passive"))
    )
    (net (code "35") (name "/VSYS") (class "Default")
      (node (ref "C10") (pin "P$1") (pinfunction "P$1_P$1") (pintype "passive"))
      (node (ref "C21") (pin "P$1") (pinfunction "P$1_P$1") (pintype "passive"))
      (node (ref "C41") (pin "P$2") (pinfunction "P$2_P$2") (pintype "passive"))
      (node (ref "C48") (pin "P$1") (pinfunction "P$1_P$1") (pintype "passive"))
      (node (ref "C49") (pin "P$1") (pinfunction "P$1_P$1") (pintype "passive"))
      (node (ref "C5") (pin "P$1") (pinfunction "P$1_P$1") (pintype "passive"))
      (node (ref "C6") (pin "P$1") (pinfunction "P$1_P$1") (pintype "passive"))
      (node (ref "C7") (pin "P$1") (pinfunction "P$1_P$1") (pintype "passive"))
      (node (ref "C8") (pin "P$1") (pinfunction "P$1_P$1") (pintype "passive"))
      (node (ref "C9") (pin "P$1") (pinfunction "P$1_P$1") (pintype "passive"))
      (node (ref "CON3") (pin "P$4") (pinfunction "P$4_P$4") (pintype "passive"))
      (node (ref "IC1") (pin "P$22") (pinfunction "VSYS_P$22") (pintype "passive"))
      (node (ref "PAD7") (pin "P$1") (pinfunction "P$1_P$1") (pintype "passive"))
      (node (ref "Q4") (pin "P$5") (pinfunction "D_P$5") (pintype "passive"))
      (node (ref "Q4") (pin "P$6") (pinfunction "D_P$6") (pintype "passive"))
      (node (ref "Q4") (pin "P$7") (pinfunction "D_P$7") (pintype "passive"))
      (node (ref "Q4") (pin "P$8") (pinfunction "D_P$8") (pintype "passive"))
      (node (ref "Q4") (pin "P$9") (pinfunction "D_P$9") (pintype "passive"))
      (node (ref "Q7") (pin "P$5") (pinfunction "S_P$5") (pintype "passive"))
      (node (ref "Q7") (pin "P$6") (pinfunction "S_P$6") (pintype "passive"))
      (node (ref "Q7") (pin "P$7") (pinfunction "S_P$7") (pintype "passive"))
      (node (ref "Q7") (pin "P$8") (pinfunction "S_P$8") (pintype "passive"))
      (node (ref "Q7") (pin "P$9") (pinfunction "S_P$9") (pintype "passive"))
    )
    (net (code "36") (name "/~{PROCHOT}") (class "Default")
      (node (ref "IC1") (pin "P$11") (pinfunction "~{PROCHOT}_P$11") (pintype "passive"))
      (node (ref "R25") (pin "P$1") (pinfunction "P$1_P$1") (pintype "passive"))
    )
    (net (code "37") (name "/~{RESET}") (class "Default")
      (node (ref "J100") (pin "5") (pinfunction "~{RESE}T_5") (pintype "power_in"))
      (node (ref "PAD4") (pin "P$1") (pinfunction "P$1_P$1") (pintype "passive"))
      (node (ref "U$1") (pin "P$7") (pinfunction "~{RESET}_P$7") (pintype "passive"))
      (node (ref "U1") (pin "19") (pinfunction "PA0/~{RESET}/UPDI/AIN0/LUT0-IN0_19") (pintype "passive"))
    )
    (net (code "38") (name "/~{SS}") (class "Default")
      (node (ref "U$1") (pin "P$6") (pinfunction "SS_P$6") (pintype "passive"))
      (node (ref "U1") (pin "18") (pinfunction "PC3/~{SS}/WO3/LUT1-IN0_18") (pintype "passive"))
    )
    (net (code "39") (name "DGND") (class "Default")
      (node (ref "C25") (pin "P$2") (pinfunction "P$2_P$2") (pintype "passive"))
      (node (ref "C29") (pin "P$1") (pinfunction "P$1_P$1") (pintype "passive"))
      (node (ref "C31") (pin "P$2") (pinfunction "P$2_P$2") (pintype "passive"))
      (node (ref "C32") (pin "P$2") (pinfunction "P$2_P$2") (pintype "passive"))
      (node (ref "C33") (pin "P$2") (pinfunction "P$2_P$2") (pintype "passive"))
      (node (ref "C34") (pin "P$2") (pinfunction "P$2_P$2") (pintype "passive"))
      (node (ref "C35") (pin "P$1") (pinfunction "P$1_P$1") (pintype "passive"))
      (node (ref "C36") (pin "P$1") (pinfunction "P$1_P$1") (pintype "passive"))
      (node (ref "C37") (pin "P$1") (pinfunction "P$1_P$1") (pintype "passive"))
      (node (ref "C46") (pin "P$1") (pinfunction "P$1_P$1") (pintype "passive"))
      (node (ref "C47") (pin "P$2") (pinfunction "P$2_P$2") (pintype "passive"))
      (node (ref "Q10") (pin "2") (pinfunction "S_2") (pintype "passive"))
      (node (ref "R1") (pin "P$2") (pinfunction "P$2_P$2") (pintype "passive"))
      (node (ref "R27") (pin "P$1") (pinfunction "P$1_P$1") (pintype "passive"))
      (node (ref "R30") (pin "P$1") (pinfunction "P$1_P$1") (pintype "passive"))
      (node (ref "R34") (pin "P$1") (pinfunction "P$1_P$1") (pintype "passive"))
      (node (ref "R51") (pin "P$1") (pinfunction "P$1_P$1") (pintype "passive"))
      (node (ref "R7") (pin "P$1") (pinfunction "P$1_P$1") (pintype "passive"))
    )
    (net (code "40") (name "GNDI") (class "Default")
      (node (ref "C1") (pin "P$2") (pinfunction "P$2_P$2") (pintype "passive"))
      (node (ref "C11") (pin "P$2") (pinfunction "P$2_P$2") (pintype "passive"))
      (node (ref "C2") (pin "P$1") (pinfunction "P$1_P$1") (pintype "passive"))
      (node (ref "J100") (pin "6") (pinfunction "GND_6") (pintype "passive"))
      (node (ref "PAD10") (pin "P$1") (pinfunction "P$1_P$1") (pintype "passive"))
      (node (ref "Q5") (pin "2") (pinfunction "S_2") (pintype "passive"))
      (node (ref "Q6") (pin "2") (pinfunction "S_2") (pintype "passive"))
      (node (ref "Q8") (pin "2") (pinfunction "S_2") (pintype "passive"))
      (node (ref "R1") (pin "P$1") (pinfunction "P$1_P$1") (pintype "passive"))
      (node (ref "R26") (pin "P$1") (pinfunction "P$1_P$1") (pintype "passive"))
      (node (ref "U$1") (pin "P$1") (pinfunction "GND_P$1") (pintype "passive"))
      (node (ref "U1") (pin "21") (pinfunction "EXT_PAD_21") (pintype "power_in"))
      (node (ref "U1") (pin "3") (pinfunction "GND_3") (pintype "power_in"))
    )
    (net (code "41") (name "Net-(C12-PadP$2)") (class "Default")
      (node (ref "C12") (pin "P$2") (pinfunction "P$2_P$2") (pintype "passive"))
      (node (ref "C17") (pin "P$2") (pinfunction "P$2_P$2") (pintype "passive"))
      (node (ref "Q1") (pin "P$5") (pinfunction "D_P$5") (pintype "passive"))
      (node (ref "Q1") (pin "P$6") (pinfunction "D_P$6") (pintype "passive"))
      (node (ref "Q1") (pin "P$7") (pinfunction "D_P$7") (pintype "passive"))
      (node (ref "Q1") (pin "P$8") (pinfunction "D_P$8") (pintype "passive"))
      (node (ref "Q1") (pin "P$9") (pinfunction "D_P$9") (pintype "passive"))
      (node (ref "R12") (pin "P$1") (pinfunction "P$1_P$1") (pintype "passive"))
      (node (ref "R2") (pin "P$2") (pinfunction "P$2_P$2") (pintype "passive"))
    )
    (net (code "42") (name "Net-(C18-PadP$2)") (class "Default")
      (node (ref "C18") (pin "P$2") (pinfunction "P$2_P$2") (pintype "passive"))
      (node (ref "R3") (pin "P$1") (pinfunction "P$1_P$1") (pintype "passive"))
      (node (ref "R4") (pin "P$1") (pinfunction "P$1_P$1") (pintype "passive"))
    )
    (net (code "43") (name "Net-(C32-PadP$1)") (class "Default")
      (node (ref "C32") (pin "P$1") (pinfunction "P$1_P$1") (pintype "passive"))
      (node (ref "R23") (pin "P$2") (pinfunction "P$2_P$2") (pintype "passive"))
    )
    (net (code "44") (name "Net-(C33-PadP$1)") (class "Default")
      (node (ref "C33") (pin "P$1") (pinfunction "P$1_P$1") (pintype "passive"))
      (node (ref "R22") (pin "P$1") (pinfunction "P$1_P$1") (pintype "passive"))
    )
    (net (code "45") (name "Net-(C38-PadP$2)") (class "Default")
      (node (ref "C38") (pin "P$2") (pinfunction "P$2_P$2") (pintype "passive"))
      (node (ref "R38") (pin "P$2") (pinfunction "P$2_P$2") (pintype "passive"))
      (node (ref "U2") (pin "P$2") (pinfunction "P$2_P$2") (pintype "passive"))
    )
    (net (code "46") (name "Net-(D2-PadC)") (class "Default")
      (node (ref "D2") (pin "C") (pinfunction "C_C") (pintype "passive"))
      (node (ref "D3") (pin "C") (pinfunction "C_C") (pintype "passive"))
      (node (ref "R38") (pin "P$1") (pinfunction "P$1_P$1") (pintype "passive"))
    )
    (net (code "47") (name "Net-(IC1-SRN)") (class "Default")
      (node (ref "IC1") (pin "P$19") (pinfunction "SRN_P$19") (pintype "passive"))
      (node (ref "R16") (pin "P$1") (pinfunction "P$1_P$1") (pintype "passive"))
    )
    (net (code "48") (name "Net-(IC1-SRP)") (class "Default")
      (node (ref "IC1") (pin "P$20") (pinfunction "SRP_P$20") (pintype "passive"))
      (node (ref "R15") (pin "P$1") (pinfunction "P$1_P$1") (pintype "passive"))
    )
    (net (code "49") (name "Net-(PAD12-PadP$1)") (class "Default")
      (node (ref "PAD12") (pin "P$1") (pinfunction "P$1_P$1") (pintype "passive"))
      (node (ref "Q9AB") (pin "E1") (pinfunction "E1_E1") (pintype "passive"))
      (node (ref "R10") (pin "P$2") (pinfunction "P$2_P$2") (pintype "passive"))
    )
    (net (code "50") (name "Net-(Q5-6-D1)") (class "Default")
      (node (ref "C23") (pin "P$2") (pinfunction "P$2_P$2") (pintype "passive"))
      (node (ref "C24") (pin "P$2") (pinfunction "P$2_P$2") (pintype "passive"))
      (node (ref "C3") (pin "P$2") (pinfunction "P$2_P$2") (pintype "passive"))
      (node (ref "C4") (pin "P$2") (pinfunction "P$2_P$2") (pintype "passive"))
      (node (ref "C44") (pin "P$2") (pinfunction "P$2_P$2") (pintype "passive"))
      (node (ref "C45") (pin "P$2") (pinfunction "P$2_P$2") (pintype "passive"))
      (node (ref "C53") (pin "P$1") (pinfunction "P$1_P$1") (pintype "passive"))
      (node (ref "Q5-6") (pin "P$5_P$6") (pinfunction "D1_P$5_P$6") (pintype "passive"))
      (node (ref "R11") (pin "P$1") (pinfunction "P$1_P$1") (pintype "passive"))
      (node (ref "R2") (pin "P$1") (pinfunction "P$1_P$1") (pintype "passive"))
    )
    (net (code "51") (name "Net-(Q5-6-G1)") (class "Default")
      (node (ref "C22") (pin "P$1") (pinfunction "P$1_P$1") (pintype "passive"))
      (node (ref "Q5-6") (pin "P$2") (pinfunction "G2_P$2") (pintype "passive"))
      (node (ref "Q5-6") (pin "P$4") (pinfunction "G1_P$4") (pintype "passive"))
      (node (ref "Q9AB") (pin "C1") (pinfunction "C1_C1") (pintype "passive"))
      (node (ref "R14") (pin "P$1") (pinfunction "P$1_P$1") (pintype "passive"))
      (node (ref "R9") (pin "P$1") (pinfunction "P$1_P$1") (pintype "passive"))
    )
    (net (code "52") (name "Net-(Q5-6-S1)") (class "Default")
      (node (ref "C22") (pin "P$2") (pinfunction "P$2_P$2") (pintype "passive"))
      (node (ref "D1") (pin "P$1") (pinfunction "P$1_P$1") (pintype "passive"))
      (node (ref "Q5-6") (pin "P$1") (pinfunction "S2_P$1") (pintype "passive"))
      (node (ref "Q5-6") (pin "P$3") (pinfunction "S1_P$3") (pintype "passive"))
      (node (ref "R10") (pin "P$1") (pinfunction "P$1_P$1") (pintype "passive"))
      (node (ref "R9") (pin "P$2") (pinfunction "P$2_P$2") (pintype "passive"))
    )
    (net (code "53") (name "Net-(Q5-D)") (class "Default")
      (node (ref "Q5") (pin "3") (pinfunction "D_3") (pintype "passive"))
      (node (ref "R28") (pin "P$2") (pinfunction "2_P$2") (pintype "passive"))
    )
    (net (code "54") (name "Net-(Q6-D)") (class "Default")
      (node (ref "Q6") (pin "3") (pinfunction "D_3") (pintype "passive"))
      (node (ref "R5") (pin "P$2") (pinfunction "2_P$2") (pintype "passive"))
    )
    (net (code "55") (name "Net-(Q6-G)") (class "Default")
      (node (ref "Q6") (pin "1") (pinfunction "G_1") (pintype "passive"))
      (node (ref "U1") (pin "11") (pinfunction "PB3/TOSC1/RXD/WO0_11") (pintype "passive"))
    )
    (net (code "56") (name "Net-(Q8-D)") (class "Default")
      (node (ref "Q8") (pin "3") (pinfunction "D_3") (pintype "passive"))
      (node (ref "R29") (pin "P$2") (pinfunction "2_P$2") (pintype "passive"))
    )
    (net (code "57") (name "Net-(Q8-G)") (class "Default")
      (node (ref "Q8") (pin "1") (pinfunction "G_1") (pintype "passive"))
      (node (ref "U1") (pin "9") (pinfunction "PB5/CLKOUT/AIN8/AINP1/WO2_9") (pintype "passive"))
    )
    (net (code "58") (name "Net-(Q9AB-PadB1)") (class "Default")
      (node (ref "Q9AB") (pin "B1") (pinfunction "B1_B1") (pintype "passive"))
      (node (ref "Q9AB") (pin "C2") (pinfunction "C2_C2") (pintype "passive"))
    )
    (net (code "59") (name "Net-(Q10-D)") (class "Default")
      (node (ref "Q10") (pin "3") (pinfunction "D_3") (pintype "passive"))
      (node (ref "Q9AB") (pin "B2") (pinfunction "B2_B2") (pintype "passive"))
      (node (ref "R17") (pin "P$1") (pinfunction "P$1_P$1") (pintype "passive"))
    )
    (net (code "60") (name "Net-(R5-1)") (class "Default")
      (node (ref "LED1") (pin "1") (pintype "power_in"))
      (node (ref "R5") (pin "P$1") (pinfunction "1_P$1") (pintype "passive"))
    )
    (net (code "61") (name "Net-(R28-1)") (class "Default")
      (node (ref "LED1") (pin "4") (pintype "power_in"))
      (node (ref "R28") (pin "P$1") (pinfunction "1_P$1") (pintype "passive"))
    )
    (net (code "62") (name "Net-(R29-1)") (class "Default")
      (node (ref "LED1") (pin "5") (pintype "power_in"))
      (node (ref "R29") (pin "P$1") (pinfunction "1_P$1") (pintype "passive"))
    )
    (net (code "63") (name "Net-(U1-PA1{slash}BREAK{slash}AIN1{slash}TXD{slash}MOSI{slash}SDA{slash}LUT0-IN1)") (class "Default")
      (node (ref "R20") (pin "P$2") (pinfunction "P$2_P$2") (pintype "passive"))
      (node (ref "U1") (pin "20") (pinfunction "PA1/BREAK/AIN1/TXD/MOSI/SDA/LUT0-IN1_20") (pintype "passive"))
    )
    (net (code "64") (name "Net-(U1-PA2{slash}EVOUT0{slash}AIN2{slash}RXD{slash}MISO{slash}SCL{slash}LUT0-IN2)") (class "Default")
      (node (ref "C11") (pin "P$1") (pinfunction "P$1_P$1") (pintype "passive"))
      (node (ref "R20") (pin "P$1") (pinfunction "P$1_P$1") (pintype "passive"))
      (node (ref "R24") (pin "P$1") (pinfunction "P$1_P$1") (pintype "passive"))
      (node (ref "U1") (pin "1") (pinfunction "PA2/EVOUT0/AIN2/RXD/MISO/SCL/LUT0-IN2_1") (pintype "passive"))
    )
    (net (code "65") (name "Net-(U1-PA4{slash}AIN4{slash}X0_Y0{slash}XDIR{slash}~{SS}{slash}WO4{slash}WOA{slash}LUT0-OUT)") (class "Default")
      (node (ref "R6") (pin "P$2") (pinfunction "P$2_P$2") (pintype "passive"))
      (node (ref "U1") (pin "5") (pinfunction "PA4/AIN4/X0_Y0/XDIR/~{SS}/WO4/WOA/LUT0-OUT_5") (pintype "passive"))
    )
    (net (code "66") (name "Net-(U1-PB4{slash}AIN9{slash}AINN1{slash}WO1{slash}LUT0-OUT)") (class "Default")
      (node (ref "R21") (pin "P$2") (pinfunction "P$2_P$2") (pintype "passive"))
      (node (ref "U1") (pin "10") (pinfunction "PB4/AIN9/AINN1/WO1/LUT0-OUT_10") (pintype "passive"))
    )
    (net (code "67") (name "PGND") (class "Default")
      (node (ref "C10") (pin "P$2") (pinfunction "P$2_P$2") (pintype "passive"))
      (node (ref "C12") (pin "P$1") (pinfunction "P$1_P$1") (pintype "passive"))
      (node (ref "C17") (pin "P$1") (pinfunction "P$1_P$1") (pintype "passive"))
      (node (ref "C18") (pin "P$1") (pinfunction "P$1_P$1") (pintype "passive"))
      (node (ref "C19") (pin "P$2") (pinfunction "P$2_P$2") (pintype "passive"))
      (node (ref "C20") (pin "P$2") (pinfunction "P$2_P$2") (pintype "passive"))
      (node (ref "C21") (pin "P$2") (pinfunction "P$2_P$2") (pintype "passive"))
      (node (ref "C23") (pin "P$1") (pinfunction "P$1_P$1") (pintype "passive"))
      (node (ref "C24") (pin "P$1") (pinfunction "P$1_P$1") (pintype "passive"))
      (node (ref "C26") (pin "2") (pinfunction "2_2") (pintype "passive"))
      (node (ref "C28") (pin "P$1") (pinfunction "P$1_P$1") (pintype "passive"))
      (node (ref "C3") (pin "P$1") (pinfunction "P$1_P$1") (pintype "passive"))
      (node (ref "C30") (pin "P$2") (pinfunction "P$2_P$2") (pintype "passive"))
      (node (ref "C38") (pin "P$1") (pinfunction "P$1_P$1") (pintype "passive"))
      (node (ref "C39") (pin "P$1") (pinfunction "P$1_P$1") (pintype "passive"))
      (node (ref "C4") (pin "P$1") (pinfunction "P$1_P$1") (pintype "passive"))
      (node (ref "C41") (pin "P$1") (pinfunction "P$1_P$1") (pintype "passive"))
      (node (ref "C44") (pin "P$1") (pinfunction "P$1_P$1") (pintype "passive"))
      (node (ref "C45") (pin "P$1") (pinfunction "P$1_P$1") (pintype "passive"))
      (node (ref "C48") (pin "P$2") (pinfunction "P$2_P$2") (pintype "passive"))
      (node (ref "C49") (pin "P$2") (pinfunction "P$2_P$2") (pintype "passive"))
      (node (ref "C5") (pin "P$2") (pinfunction "P$2_P$2") (pintype "passive"))
      (node (ref "C53") (pin "P$2") (pinfunction "P$2_P$2") (pintype "passive"))
      (node (ref "C6") (pin "P$2") (pinfunction "P$2_P$2") (pintype "passive"))
      (node (ref "C7") (pin "P$2") (pinfunction "P$2_P$2") (pintype "passive"))
      (node (ref "C8") (pin "P$2") (pinfunction "P$2_P$2") (pintype "passive"))
      (node (ref "C9") (pin "P$2") (pinfunction "P$2_P$2") (pintype "passive"))
      (node (ref "CON1") (pin "P$3") (pinfunction "P$3_P$3") (pintype "passive"))
      (node (ref "CON1") (pin "P$4") (pinfunction "VSS_P$4") (pintype "passive"))
      (node (ref "CON1") (pin "P$5") (pinfunction "VSS_P$5") (pintype "passive"))
      (node (ref "CON2") (pin "P$1") (pinfunction "P$1_P$1") (pintype "passive"))
      (node (ref "CON2") (pin "P$4") (pinfunction "P$4_P$4") (pintype "passive"))
      (node (ref "CON3") (pin "P$2") (pinfunction "P$2_P$2") (pintype "passive"))
      (node (ref "CON3") (pin "P$3") (pinfunction "P$3_P$3") (pintype "passive"))
      (node (ref "D1") (pin "P$2") (pinfunction "P$2_P$2") (pintype "passive"))
      (node (ref "IC1") (pin "P$27") (pinfunction "PGND_P$27") (pintype "passive"))
      (node (ref "IC1") (pin "P$33") (pinfunction "PGND_P$33") (pintype "passive"))
      (node (ref "PAD3") (pin "P$1") (pinfunction "P$1_P$1") (pintype "passive"))
      (node (ref "Q2") (pin "P$1") (pinfunction "S_P$1") (pintype "passive"))
      (node (ref "Q2") (pin "P$2") (pinfunction "S_P$2") (pintype "passive"))
      (node (ref "Q2") (pin "P$3") (pinfunction "S_P$3") (pintype "passive"))
      (node (ref "Q3") (pin "P$1") (pinfunction "S_P$1") (pintype "passive"))
      (node (ref "Q3") (pin "P$2") (pinfunction "S_P$2") (pintype "passive"))
      (node (ref "Q3") (pin "P$3") (pinfunction "S_P$3") (pintype "passive"))
      (node (ref "Q9AB") (pin "E2") (pinfunction "E2_E2") (pintype "passive"))
      (node (ref "R14") (pin "P$2") (pinfunction "P$2_P$2") (pintype "passive"))
      (node (ref "U2") (pin "P$3") (pinfunction "P$3_P$3") (pintype "passive"))
    )
    (net (code "68") (name "VDDA") (class "Default")
      (node (ref "C29") (pin "P$2") (pinfunction "P$2_P$2") (pintype "passive"))
      (node (ref "IC1") (pin "P$7") (pinfunction "VDDA_P$7") (pintype "passive"))
      (node (ref "R18") (pin "P$2") (pinfunction "P$2_P$2") (pintype "passive"))
      (node (ref "R19") (pin "P$2") (pinfunction "P$2_P$2") (pintype "passive"))
      (node (ref "R50") (pin "P$2") (pinfunction "P$2_P$2") (pintype "passive"))
    )
    (net (code "69") (name "unconnected-(IC1-OTG{slash}VAP-PadP$5)") (class "Default")
      (node (ref "IC1") (pin "P$5") (pinfunction "OTG/VAP_P$5") (pintype "passive"))
    )
    (net (code "70") (name "unconnected-(U1-PA3{slash}EXTCLK{slash}AIN3{slash}XCK{slash}SCK{slash}WO3-Pad2)") (class "Default")
      (node (ref "U1") (pin "2") (pinfunction "PA3/EXTCLK/AIN3/XCK/SCK/WO3_2") (pintype "passive"))
    )
    (net (code "71") (name "unconnected-(U1-PA5{slash}AIN5{slash}X1_Y1{slash}OUT{slash}WO5{slash}WO{slash}WOB-Pad6)") (class "Default")
      (node (ref "U1") (pin "6") (pinfunction "PA5/AIN5/X1_Y1/OUT/WO5/WO/WOB_6") (pintype "passive"))
    )
    (net (code "72") (name "unconnected-(U1-PA6{slash}AIN6{slash}X2_Y2{slash}AINN0{slash}OUT-Pad7)") (class "Default")
      (node (ref "U1") (pin "7") (pinfunction "PA6/AIN6/X2_Y2/AINN0/OUT_7") (pintype "passive"))
    )
    (net (code "73") (name "unconnected-(U1-PA7{slash}AIN7{slash}X3_Y3{slash}AINP0{slash}LUT1-OUT-Pad8)") (class "Default")
      (node (ref "U1") (pin "8") (pinfunction "PA7/AIN7/X3_Y3/AINP0/LUT1-OUT_8") (pintype "passive"))
    )
    (net (code "74") (name "unconnected-(U1-PB2{slash}TOSC2{slash}EVOUT1{slash}TXD{slash}WO2-Pad12)") (class "Default")
      (node (ref "U1") (pin "12") (pinfunction "PB2/TOSC2/EVOUT1/TXD/WO2_12") (pintype "passive"))
    )
  )
)
